# M885E.net
KiCad netlist of a schematic drawn in EAGLE
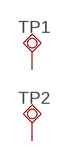
[diagram p0: schematic, sheet 1, part 1 of 2]
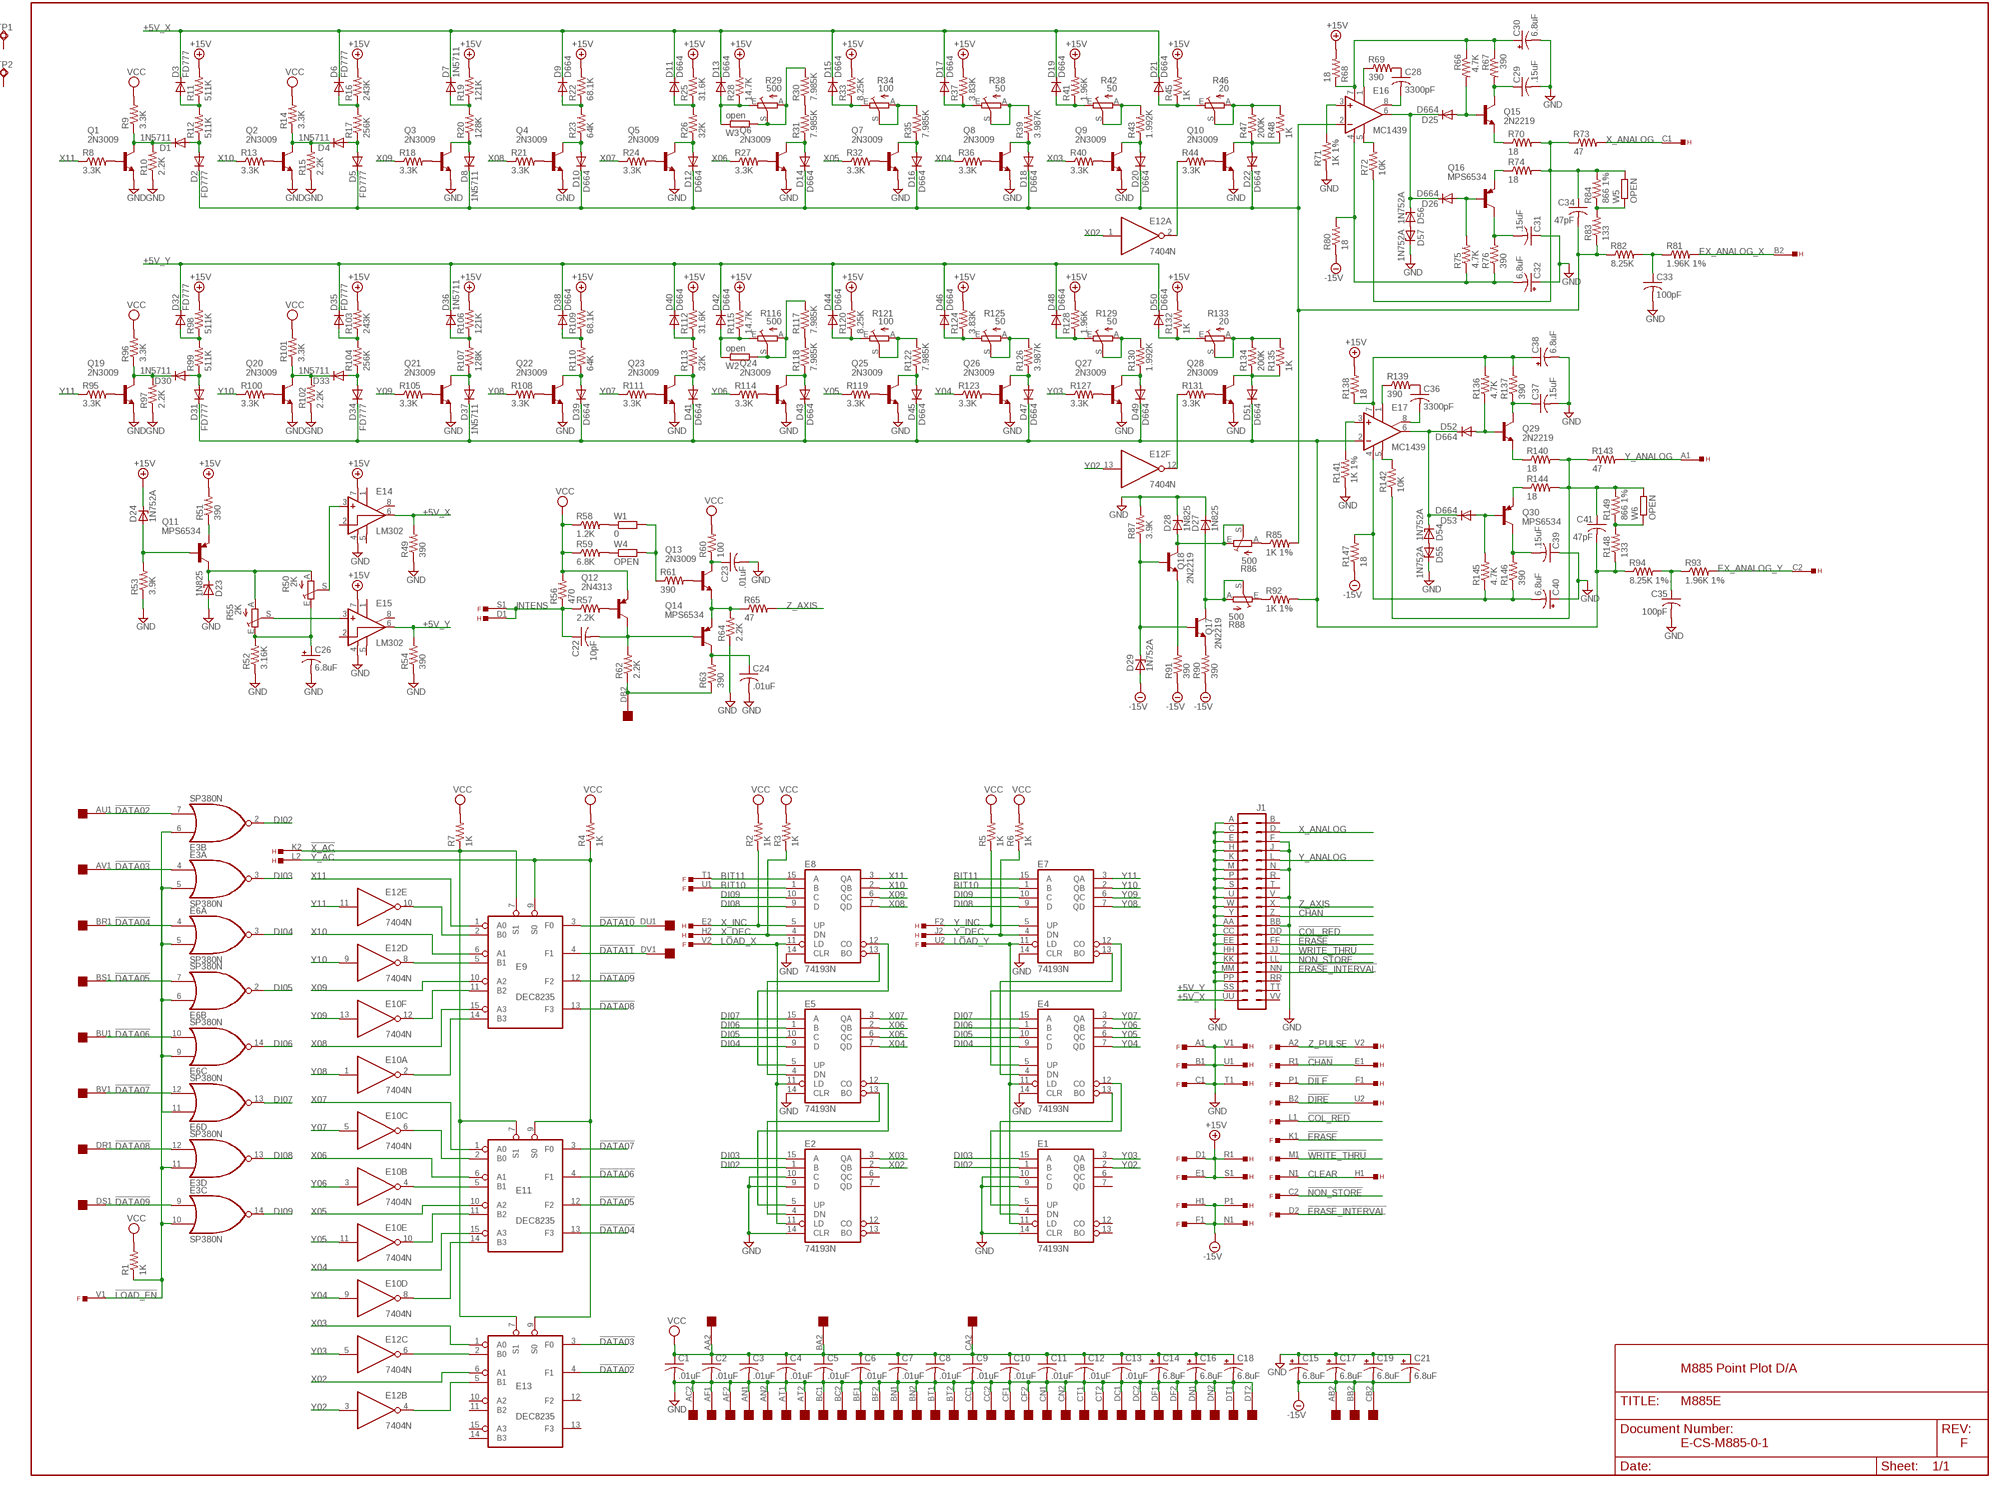
[diagram p1: schematic, sheet 1, part 2 of 2]

(export (version "E")
  (design (tool "Eeschema 10.0.6"))
  (components
    (comp (ref "C1")
      (value ".01uF")
      (footprint "eagle-import:C063-025X075")
      (libsource (lib "eagle-import") (part "C-US"))
    )
    (comp (ref "C2")
      (value ".01uF")
      (footprint "eagle-import:C063-025X075")
      (libsource (lib "eagle-import") (part "C-US"))
    )
    (comp (ref "C3")
      (value ".01uF")
      (footprint "eagle-import:C063-025X075")
      (libsource (lib "eagle-import") (part "C-US"))
    )
    (comp (ref "C4")
      (value ".01uF")
      (footprint "eagle-import:C063-025X075")
      (libsource (lib "eagle-import") (part "C-US"))
    )
    (comp (ref "C5")
      (value ".01uF")
      (footprint "eagle-import:C063-025X075")
      (libsource (lib "eagle-import") (part "C-US"))
    )
    (comp (ref "C6")
      (value ".01uF")
      (footprint "eagle-import:C063-025X075")
      (libsource (lib "eagle-import") (part "C-US"))
    )
    (comp (ref "C7")
      (value ".01uF")
      (footprint "eagle-import:C063-025X075")
      (libsource (lib "eagle-import") (part "C-US"))
    )
    (comp (ref "C8")
      (value ".01uF")
      (footprint "eagle-import:C063-025X075")
      (libsource (lib "eagle-import") (part "C-US"))
    )
    (comp (ref "C9")
      (value ".01uF")
      (footprint "eagle-import:C063-025X075")
      (libsource (lib "eagle-import") (part "C-US"))
    )
    (comp (ref "C10")
      (value ".01uF")
      (footprint "eagle-import:C063-025X075")
      (libsource (lib "eagle-import") (part "C-US"))
    )
    (comp (ref "C11")
      (value ".01uF")
      (footprint "eagle-import:C063-025X075")
      (libsource (lib "eagle-import") (part "C-US"))
    )
    (comp (ref "C12")
      (value ".01uF")
      (footprint "eagle-import:C063-025X075")
      (libsource (lib "eagle-import") (part "C-US"))
    )
    (comp (ref "C13")
      (value ".01uF")
      (footprint "eagle-import:C063-025X075")
      (libsource (lib "eagle-import") (part "C-US"))
    )
    (comp (ref "C14")
      (value "6.8uF")
      (footprint "eagle-import:E12-8")
      (libsource (lib "eagle-import") (part "CPOL-USE20-8AXIAL"))
    )
    (comp (ref "C15")
      (value "6.8uF")
      (footprint "eagle-import:E12-8")
      (libsource (lib "eagle-import") (part "CPOL-USE20-8AXIAL"))
    )
    (comp (ref "C16")
      (value "6.8uF")
      (footprint "eagle-import:E12-8")
      (libsource (lib "eagle-import") (part "CPOL-USE20-8AXIAL"))
    )
    (comp (ref "C17")
      (value "6.8uF")
      (footprint "eagle-import:E12-8")
      (libsource (lib "eagle-import") (part "CPOL-USE20-8AXIAL"))
    )
    (comp (ref "C18")
      (value "6.8uF")
      (footprint "eagle-import:E12-8")
      (libsource (lib "eagle-import") (part "CPOL-USE20-8AXIAL"))
    )
    (comp (ref "C19")
      (value "6.8uF")
      (footprint "eagle-import:E12-8")
      (libsource (lib "eagle-import") (part "CPOL-USE20-8AXIAL"))
    )
    (comp (ref "C21")
      (value "6.8uF")
      (footprint "eagle-import:E12-8")
      (libsource (lib "eagle-import") (part "CPOL-USE20-8AXIAL"))
    )
    (comp (ref "C22")
      (value "10pF")
      (footprint "eagle-import:C063-025X075")
      (libsource (lib "eagle-import") (part "C-US"))
    )
    (comp (ref "C23")
      (value ".01uF")
      (footprint "eagle-import:C063-025X075")
      (libsource (lib "eagle-import") (part "C-US"))
    )
    (comp (ref "C24")
      (value ".01uF")
      (footprint "eagle-import:C063-025X075")
      (libsource (lib "eagle-import") (part "C-US"))
    )
    (comp (ref "C26")
      (value "6.8uF")
      (footprint "eagle-import:E12-8")
      (libsource (lib "eagle-import") (part "CPOL-USE20-8AXIAL"))
    )
    (comp (ref "C28")
      (value "3300pF")
      (footprint "eagle-import:C150-054X183")
      (libsource (lib "eagle-import") (part "C-US150-054X183"))
    )
    (comp (ref "C29")
      (value ".15uF")
      (footprint "eagle-import:C150-054X183")
      (libsource (lib "eagle-import") (part "C-US150-054X183"))
    )
    (comp (ref "C30")
      (value "6.8uF")
      (footprint "eagle-import:E12-8")
      (libsource (lib "eagle-import") (part "CPOL-USE20-8AXIAL"))
    )
    (comp (ref "C31")
      (value ".15uF")
      (footprint "eagle-import:C150-054X183")
      (libsource (lib "eagle-import") (part "C-US150-054X183"))
    )
    (comp (ref "C32")
      (value "6.8uF")
      (footprint "eagle-import:E12-8")
      (libsource (lib "eagle-import") (part "CPOL-USE20-8AXIAL"))
    )
    (comp (ref "C33")
      (value "100pF")
      (footprint "eagle-import:C063-025X075")
      (libsource (lib "eagle-import") (part "C-US"))
    )
    (comp (ref "C34")
      (value "47pF")
      (footprint "eagle-import:C063-025X075")
      (libsource (lib "eagle-import") (part "C-US"))
    )
    (comp (ref "C35")
      (value "100pF")
      (footprint "eagle-import:C063-025X075")
      (libsource (lib "eagle-import") (part "C-US"))
    )
    (comp (ref "C36")
      (value "3300pF")
      (footprint "eagle-import:C150-054X183")
      (libsource (lib "eagle-import") (part "C-US150-054X183"))
    )
    (comp (ref "C37")
      (value ".15uF")
      (footprint "eagle-import:C150-054X183")
      (libsource (lib "eagle-import") (part "C-US150-054X183"))
    )
    (comp (ref "C38")
      (value "6.8uF")
      (footprint "eagle-import:E12-8")
      (libsource (lib "eagle-import") (part "CPOL-USE20-8AXIAL"))
    )
    (comp (ref "C39")
      (value ".15uF")
      (footprint "eagle-import:C150-054X183")
      (libsource (lib "eagle-import") (part "C-US150-054X183"))
    )
    (comp (ref "C40")
      (value "6.8uF")
      (footprint "eagle-import:E12-8")
      (libsource (lib "eagle-import") (part "CPOL-USE20-8AXIAL"))
    )
    (comp (ref "C41")
      (value "47pF")
      (footprint "eagle-import:C063-025X075")
      (libsource (lib "eagle-import") (part "C-US"))
    )
    (comp (ref "D1")
      (value "1N5711")
      (footprint "eagle-import:DO35-10")
      (libsource (lib "eagle-import") (part "DIODE-DO35-10"))
    )
    (comp (ref "D2")
      (value "FD777")
      (footprint "eagle-import:DO35-10")
      (libsource (lib "eagle-import") (part "DIODE-DO35-10"))
    )
    (comp (ref "D3")
      (value "FD777")
      (footprint "eagle-import:DO35-10")
      (libsource (lib "eagle-import") (part "DIODE-DO35-10"))
    )
    (comp (ref "D4")
      (value "1N5711")
      (footprint "eagle-import:DO35-10")
      (libsource (lib "eagle-import") (part "DIODE-DO35-10"))
    )
    (comp (ref "D5")
      (value "FD777")
      (footprint "eagle-import:DO35-10")
      (libsource (lib "eagle-import") (part "DIODE-DO35-10"))
    )
    (comp (ref "D6")
      (value "FD777")
      (footprint "eagle-import:DO35-10")
      (libsource (lib "eagle-import") (part "DIODE-DO35-10"))
    )
    (comp (ref "D7")
      (value "1N5711")
      (footprint "eagle-import:DO35-10")
      (libsource (lib "eagle-import") (part "DIODE-DO35-10"))
    )
    (comp (ref "D8")
      (value "1N5711")
      (footprint "eagle-import:DO35-10")
      (libsource (lib "eagle-import") (part "DIODE-DO35-10"))
    )
    (comp (ref "D9")
      (value "D664")
      (footprint "eagle-import:DO35-10")
      (libsource (lib "eagle-import") (part "DIODE-DO35-10"))
    )
    (comp (ref "D10")
      (value "D664")
      (footprint "eagle-import:DO35-10")
      (libsource (lib "eagle-import") (part "DIODE-DO35-10"))
    )
    (comp (ref "D11")
      (value "D664")
      (footprint "eagle-import:DO35-10")
      (libsource (lib "eagle-import") (part "DIODE-DO35-10"))
    )
    (comp (ref "D12")
      (value "D664")
      (footprint "eagle-import:DO35-10")
      (libsource (lib "eagle-import") (part "DIODE-DO35-10"))
    )
    (comp (ref "D13")
      (value "D664")
      (footprint "eagle-import:DO35-10")
      (libsource (lib "eagle-import") (part "DIODE-DO35-10"))
    )
    (comp (ref "D14")
      (value "D664")
      (footprint "eagle-import:DO35-10")
      (libsource (lib "eagle-import") (part "DIODE-DO35-10"))
    )
    (comp (ref "D15")
      (value "D664")
      (footprint "eagle-import:DO35-10")
      (libsource (lib "eagle-import") (part "DIODE-DO35-10"))
    )
    (comp (ref "D16")
      (value "D664")
      (footprint "eagle-import:DO35-10")
      (libsource (lib "eagle-import") (part "DIODE-DO35-10"))
    )
    (comp (ref "D17")
      (value "D664")
      (footprint "eagle-import:DO35-10")
      (libsource (lib "eagle-import") (part "DIODE-DO35-10"))
    )
    (comp (ref "D18")
      (value "D664")
      (footprint "eagle-import:DO35-10")
      (libsource (lib "eagle-import") (part "DIODE-DO35-10"))
    )
    (comp (ref "D19")
      (value "D664")
      (footprint "eagle-import:DO35-10")
      (libsource (lib "eagle-import") (part "DIODE-DO35-10"))
    )
    (comp (ref "D20")
      (value "D664")
      (footprint "eagle-import:DO35-10")
      (libsource (lib "eagle-import") (part "DIODE-DO35-10"))
    )
    (comp (ref "D21")
      (value "D664")
      (footprint "eagle-import:DO35-10")
      (libsource (lib "eagle-import") (part "DIODE-DO35-10"))
    )
    (comp (ref "D22")
      (value "D664")
      (footprint "eagle-import:DO35-10")
      (libsource (lib "eagle-import") (part "DIODE-DO35-10"))
    )
    (comp (ref "D23")
      (value "1N825")
      (footprint "eagle-import:DO35Z10")
      (libsource (lib "eagle-import") (part "ZENER-DIODEDO35Z10"))
    )
    (comp (ref "D24")
      (value "1N752A")
      (footprint "eagle-import:DO35Z10")
      (libsource (lib "eagle-import") (part "ZENER-DIODEDO35Z10"))
    )
    (comp (ref "D25")
      (value "D664")
      (footprint "eagle-import:DO35-10")
      (libsource (lib "eagle-import") (part "DIODE-DO35-10"))
    )
    (comp (ref "D26")
      (value "D664")
      (footprint "eagle-import:DO35-10")
      (libsource (lib "eagle-import") (part "DIODE-DO35-10"))
    )
    (comp (ref "D27")
      (value "1N825")
      (footprint "eagle-import:DO35Z10")
      (libsource (lib "eagle-import") (part "ZENER-DIODEDO35Z10"))
    )
    (comp (ref "D28")
      (value "1N825")
      (footprint "eagle-import:DO35Z10")
      (libsource (lib "eagle-import") (part "ZENER-DIODEDO35Z10"))
    )
    (comp (ref "D29")
      (value "1N752A")
      (footprint "eagle-import:DO35Z10")
      (libsource (lib "eagle-import") (part "ZENER-DIODEDO35Z10"))
    )
    (comp (ref "D30")
      (value "1N5711")
      (footprint "eagle-import:DO35-10")
      (libsource (lib "eagle-import") (part "DIODE-DO35-10"))
    )
    (comp (ref "D31")
      (value "FD777")
      (footprint "eagle-import:DO35-10")
      (libsource (lib "eagle-import") (part "DIODE-DO35-10"))
    )
    (comp (ref "D32")
      (value "FD777")
      (footprint "eagle-import:DO35-10")
      (libsource (lib "eagle-import") (part "DIODE-DO35-10"))
    )
    (comp (ref "D33")
      (value "1N5711")
      (footprint "eagle-import:DO35-10")
      (libsource (lib "eagle-import") (part "DIODE-DO35-10"))
    )
    (comp (ref "D34")
      (value "FD777")
      (footprint "eagle-import:DO35-10")
      (libsource (lib "eagle-import") (part "DIODE-DO35-10"))
    )
    (comp (ref "D35")
      (value "FD777")
      (footprint "eagle-import:DO35-10")
      (libsource (lib "eagle-import") (part "DIODE-DO35-10"))
    )
    (comp (ref "D36")
      (value "1N5711")
      (footprint "eagle-import:DO35-10")
      (libsource (lib "eagle-import") (part "DIODE-DO35-10"))
    )
    (comp (ref "D37")
      (value "1N5711")
      (footprint "eagle-import:DO35-10")
      (libsource (lib "eagle-import") (part "DIODE-DO35-10"))
    )
    (comp (ref "D38")
      (value "D664")
      (footprint "eagle-import:DO35-10")
      (libsource (lib "eagle-import") (part "DIODE-DO35-10"))
    )
    (comp (ref "D39")
      (value "D664")
      (footprint "eagle-import:DO35-10")
      (libsource (lib "eagle-import") (part "DIODE-DO35-10"))
    )
    (comp (ref "D40")
      (value "D664")
      (footprint "eagle-import:DO35-10")
      (libsource (lib "eagle-import") (part "DIODE-DO35-10"))
    )
    (comp (ref "D41")
      (value "D664")
      (footprint "eagle-import:DO35-10")
      (libsource (lib "eagle-import") (part "DIODE-DO35-10"))
    )
    (comp (ref "D42")
      (value "D664")
      (footprint "eagle-import:DO35-10")
      (libsource (lib "eagle-import") (part "DIODE-DO35-10"))
    )
    (comp (ref "D43")
      (value "D664")
      (footprint "eagle-import:DO35-10")
      (libsource (lib "eagle-import") (part "DIODE-DO35-10"))
    )
    (comp (ref "D44")
      (value "D664")
      (footprint "eagle-import:DO35-10")
      (libsource (lib "eagle-import") (part "DIODE-DO35-10"))
    )
    (comp (ref "D45")
      (value "D664")
      (footprint "eagle-import:DO35-10")
      (libsource (lib "eagle-import") (part "DIODE-DO35-10"))
    )
    (comp (ref "D46")
      (value "D664")
      (footprint "eagle-import:DO35-10")
      (libsource (lib "eagle-import") (part "DIODE-DO35-10"))
    )
    (comp (ref "D47")
      (value "D664")
      (footprint "eagle-import:DO35-10")
      (libsource (lib "eagle-import") (part "DIODE-DO35-10"))
    )
    (comp (ref "D48")
      (value "D664")
      (footprint "eagle-import:DO35-10")
      (libsource (lib "eagle-import") (part "DIODE-DO35-10"))
    )
    (comp (ref "D49")
      (value "D664")
      (footprint "eagle-import:DO35-10")
      (libsource (lib "eagle-import") (part "DIODE-DO35-10"))
    )
    (comp (ref "D50")
      (value "D664")
      (footprint "eagle-import:DO35-10")
      (libsource (lib "eagle-import") (part "DIODE-DO35-10"))
    )
    (comp (ref "D51")
      (value "D664")
      (footprint "eagle-import:DO35-10")
      (libsource (lib "eagle-import") (part "DIODE-DO35-10"))
    )
    (comp (ref "D52")
      (value "D664")
      (footprint "eagle-import:DO35-10")
      (libsource (lib "eagle-import") (part "DIODE-DO35-10"))
    )
    (comp (ref "D53")
      (value "D664")
      (footprint "eagle-import:DO35-10")
      (libsource (lib "eagle-import") (part "DIODE-DO35-10"))
    )
    (comp (ref "D54")
      (value "1N752A")
      (footprint "eagle-import:DO35Z10")
      (libsource (lib "eagle-import") (part "ZENER-DIODEDO35Z10"))
    )
    (comp (ref "D55")
      (value "1N752A")
      (footprint "eagle-import:DO35Z10")
      (libsource (lib "eagle-import") (part "ZENER-DIODEDO35Z10"))
    )
    (comp (ref "D56")
      (value "1N752A")
      (footprint "eagle-import:DO35Z10")
      (libsource (lib "eagle-import") (part "ZENER-DIODEDO35Z10"))
    )
    (comp (ref "D57")
      (value "1N752A")
      (footprint "eagle-import:DO35Z10")
      (libsource (lib "eagle-import") (part "ZENER-DIODEDO35Z10"))
    )
    (comp (ref "E1")
      (value "74193N")
      (footprint "eagle-import:DIL16")
      (libsource (lib "eagle-import") (part "74193N"))
    )
    (comp (ref "E2")
      (value "74193N")
      (footprint "eagle-import:DIL16")
      (libsource (lib "eagle-import") (part "74193N"))
    )
    (comp (ref "E3")
      (value "SP380N")
      (footprint "eagle-import:DIL14")
      (libsource (lib "eagle-import") (part "SP380N"))
    )
    (comp (ref "E4")
      (value "74193N")
      (footprint "eagle-import:DIL16")
      (libsource (lib "eagle-import") (part "74193N"))
    )
    (comp (ref "E5")
      (value "74193N")
      (footprint "eagle-import:DIL16")
      (libsource (lib "eagle-import") (part "74193N"))
    )
    (comp (ref "E6")
      (value "SP380N")
      (footprint "eagle-import:DIL14")
      (libsource (lib "eagle-import") (part "SP380N"))
    )
    (comp (ref "E7")
      (value "74193N")
      (footprint "eagle-import:DIL16")
      (libsource (lib "eagle-import") (part "74193N"))
    )
    (comp (ref "E8")
      (value "74193N")
      (footprint "eagle-import:DIL16")
      (libsource (lib "eagle-import") (part "74193N"))
    )
    (comp (ref "E9")
      (value "DEC8235")
      (footprint "eagle-import:DIL16")
      (libsource (lib "eagle-import") (part "DEC8235"))
    )
    (comp (ref "E10")
      (value "7404N")
      (footprint "eagle-import:DIL14")
      (libsource (lib "eagle-import") (part "7404N"))
    )
    (comp (ref "E11")
      (value "DEC8235")
      (footprint "eagle-import:DIL16")
      (libsource (lib "eagle-import") (part "DEC8235"))
    )
    (comp (ref "E12")
      (value "7404N")
      (footprint "eagle-import:DIL14")
      (libsource (lib "eagle-import") (part "7404N"))
    )
    (comp (ref "E13")
      (value "DEC8235")
      (footprint "eagle-import:DIL16")
      (libsource (lib "eagle-import") (part "DEC8235"))
    )
    (comp (ref "E14")
      (value "LM302")
      (footprint "eagle-import:TO99")
      (libsource (lib "eagle-import") (part "AD504H"))
    )
    (comp (ref "E15")
      (value "LM302")
      (footprint "eagle-import:TO99")
      (libsource (lib "eagle-import") (part "AD504H"))
    )
    (comp (ref "E16")
      (value "MC1439")
      (footprint "eagle-import:TO99")
      (libsource (lib "eagle-import") (part "AD504H"))
    )
    (comp (ref "E17")
      (value "MC1439")
      (footprint "eagle-import:TO99")
      (libsource (lib "eagle-import") (part "AD504H"))
    )
    (comp (ref "F")
      (value "EDGE-TOP")
      (footprint "eagle-import:EDGE-CON2")
      (libsource (lib "eagle-import") (part "EDGE-TOP"))
    )
    (comp (ref "H")
      (value "EDGE-TOP")
      (footprint "eagle-import:EDGE-CON2")
      (libsource (lib "eagle-import") (part "EDGE-TOP"))
    )
    (comp (ref "J1")
      (value "DEC40PINH")
      (footprint "eagle-import:DEC40PINH")
      (libsource (lib "eagle-import") (part "DEC40PINH"))
    )
    (comp (ref "OMNIBUS")
      (value "QUAD")
      (footprint "eagle-import:EDGE-CON8")
      (libsource (lib "eagle-import") (part "QUAD"))
    )
    (comp (ref "Q1")
      (value "2N3009")
      (footprint "eagle-import:TO5")
      (libsource (lib "eagle-import") (part "-NPN-TO5"))
    )
    (comp (ref "Q2")
      (value "2N3009")
      (footprint "eagle-import:TO5")
      (libsource (lib "eagle-import") (part "-NPN-TO5"))
    )
    (comp (ref "Q3")
      (value "2N3009")
      (footprint "eagle-import:TO5")
      (libsource (lib "eagle-import") (part "-NPN-TO5"))
    )
    (comp (ref "Q4")
      (value "2N3009")
      (footprint "eagle-import:TO5")
      (libsource (lib "eagle-import") (part "-NPN-TO5"))
    )
    (comp (ref "Q5")
      (value "2N3009")
      (footprint "eagle-import:TO5")
      (libsource (lib "eagle-import") (part "-NPN-TO5"))
    )
    (comp (ref "Q6")
      (value "2N3009")
      (footprint "eagle-import:TO5")
      (libsource (lib "eagle-import") (part "-NPN-TO5"))
    )
    (comp (ref "Q7")
      (value "2N3009")
      (footprint "eagle-import:TO5")
      (libsource (lib "eagle-import") (part "-NPN-TO5"))
    )
    (comp (ref "Q8")
      (value "2N3009")
      (footprint "eagle-import:TO5")
      (libsource (lib "eagle-import") (part "-NPN-TO5"))
    )
    (comp (ref "Q9")
      (value "2N3009")
      (footprint "eagle-import:TO5")
      (libsource (lib "eagle-import") (part "-NPN-TO5"))
    )
    (comp (ref "Q10")
      (value "2N3009")
      (footprint "eagle-import:TO5")
      (libsource (lib "eagle-import") (part "-NPN-TO5"))
    )
    (comp (ref "Q11")
      (value "MPS6534")
      (footprint "eagle-import:TO5")
      (libsource (lib "eagle-import") (part "-PNP-TO5"))
    )
    (comp (ref "Q12")
      (value "2N4313")
      (footprint "eagle-import:TO5")
      (libsource (lib "eagle-import") (part "-PNP-TO5"))
    )
    (comp (ref "Q13")
      (value "2N3009")
      (footprint "eagle-import:TO5")
      (libsource (lib "eagle-import") (part "-NPN-TO5"))
    )
    (comp (ref "Q14")
      (value "MPS6534")
      (footprint "eagle-import:TO5")
      (libsource (lib "eagle-import") (part "-PNP-TO5"))
    )
    (comp (ref "Q15")
      (value "2N2219")
      (footprint "eagle-import:TO5")
      (libsource (lib "eagle-import") (part "-NPN-TO5"))
    )
    (comp (ref "Q16")
      (value "MPS6534")
      (footprint "eagle-import:TO5")
      (libsource (lib "eagle-import") (part "-PNP-TO5"))
    )
    (comp (ref "Q17")
      (value "2N2219")
      (footprint "eagle-import:TO5")
      (libsource (lib "eagle-import") (part "-NPN-TO5"))
    )
    (comp (ref "Q18")
      (value "2N2219")
      (footprint "eagle-import:TO5")
      (libsource (lib "eagle-import") (part "-NPN-TO5"))
    )
    (comp (ref "Q19")
      (value "2N3009")
      (footprint "eagle-import:TO5")
      (libsource (lib "eagle-import") (part "-NPN-TO5"))
    )
    (comp (ref "Q20")
      (value "2N3009")
      (footprint "eagle-import:TO5")
      (libsource (lib "eagle-import") (part "-NPN-TO5"))
    )
    (comp (ref "Q21")
      (value "2N3009")
      (footprint "eagle-import:TO5")
      (libsource (lib "eagle-import") (part "-NPN-TO5"))
    )
    (comp (ref "Q22")
      (value "2N3009")
      (footprint "eagle-import:TO5")
      (libsource (lib "eagle-import") (part "-NPN-TO5"))
    )
    (comp (ref "Q23")
      (value "2N3009")
      (footprint "eagle-import:TO5")
      (libsource (lib "eagle-import") (part "-NPN-TO5"))
    )
    (comp (ref "Q24")
      (value "2N3009")
      (footprint "eagle-import:TO5")
      (libsource (lib "eagle-import") (part "-NPN-TO5"))
    )
    (comp (ref "Q25")
      (value "2N3009")
      (footprint "eagle-import:TO5")
      (libsource (lib "eagle-import") (part "-NPN-TO5"))
    )
    (comp (ref "Q26")
      (value "2N3009")
      (footprint "eagle-import:TO5")
      (libsource (lib "eagle-import") (part "-NPN-TO5"))
    )
    (comp (ref "Q27")
      (value "2N3009")
      (footprint "eagle-import:TO5")
      (libsource (lib "eagle-import") (part "-NPN-TO5"))
    )
    (comp (ref "Q28")
      (value "2N3009")
      (footprint "eagle-import:TO5")
      (libsource (lib "eagle-import") (part "-NPN-TO5"))
    )
    (comp (ref "Q29")
      (value "2N2219")
      (footprint "eagle-import:TO5")
      (libsource (lib "eagle-import") (part "-NPN-TO5"))
    )
    (comp (ref "Q30")
      (value "MPS6534")
      (footprint "eagle-import:TO5")
      (libsource (lib "eagle-import") (part "-PNP-TO5"))
    )
    (comp (ref "R1")
      (value "1K")
      (footprint "eagle-import:0207_10")
      (libsource (lib "eagle-import") (part "R-US_0207/10"))
    )
    (comp (ref "R2")
      (value "1K")
      (footprint "eagle-import:0207_10")
      (libsource (lib "eagle-import") (part "R-US_0207/10"))
    )
    (comp (ref "R3")
      (value "1K")
      (footprint "eagle-import:0207_10")
      (libsource (lib "eagle-import") (part "R-US_0207/10"))
    )
    (comp (ref "R4")
      (value "1K")
      (footprint "eagle-import:0207_10")
      (libsource (lib "eagle-import") (part "R-US_0207/10"))
    )
    (comp (ref "R5")
      (value "1K")
      (footprint "eagle-import:0207_10")
      (libsource (lib "eagle-import") (part "R-US_0207/10"))
    )
    (comp (ref "R6")
      (value "1K")
      (footprint "eagle-import:0207_10")
      (libsource (lib "eagle-import") (part "R-US_0207/10"))
    )
    (comp (ref "R7")
      (value "1K")
      (footprint "eagle-import:0207_10")
      (libsource (lib "eagle-import") (part "R-US_0207/10"))
    )
    (comp (ref "R8")
      (value "3.3K")
      (footprint "eagle-import:0207_10")
      (libsource (lib "eagle-import") (part "R-US_0207/10"))
    )
    (comp (ref "R9")
      (value "3.3K")
      (footprint "eagle-import:0207_10")
      (libsource (lib "eagle-import") (part "R-US_0207/10"))
    )
    (comp (ref "R10")
      (value "2.2K")
      (footprint "eagle-import:0207_10")
      (libsource (lib "eagle-import") (part "R-US_0207/10"))
    )
    (comp (ref "R11")
      (value "511K")
      (footprint "eagle-import:0207_15")
      (libsource (lib "eagle-import") (part "R-US_0207/15"))
    )
    (comp (ref "R12")
      (value "511K")
      (footprint "eagle-import:0207_15")
      (libsource (lib "eagle-import") (part "R-US_0207/15"))
    )
    (comp (ref "R13")
      (value "3.3K")
      (footprint "eagle-import:0207_10")
      (libsource (lib "eagle-import") (part "R-US_0207/10"))
    )
    (comp (ref "R14")
      (value "3.3K")
      (footprint "eagle-import:0207_10")
      (libsource (lib "eagle-import") (part "R-US_0207/10"))
    )
    (comp (ref "R15")
      (value "2.2K")
      (footprint "eagle-import:0207_10")
      (libsource (lib "eagle-import") (part "R-US_0207/10"))
    )
    (comp (ref "R16")
      (value "243K")
      (footprint "eagle-import:0207_15")
      (libsource (lib "eagle-import") (part "R-US_0207/15"))
    )
    (comp (ref "R17")
      (value "256K")
      (footprint "eagle-import:0207_15")
      (libsource (lib "eagle-import") (part "R-US_0207/15"))
    )
    (comp (ref "R18")
      (value "3.3K")
      (footprint "eagle-import:0207_10")
      (libsource (lib "eagle-import") (part "R-US_0207/10"))
    )
    (comp (ref "R19")
      (value "121K")
      (footprint "eagle-import:0207_15")
      (libsource (lib "eagle-import") (part "R-US_0207/15"))
    )
    (comp (ref "R20")
      (value "128K")
      (footprint "eagle-import:0207_15")
      (libsource (lib "eagle-import") (part "R-US_0207/15"))
    )
    (comp (ref "R21")
      (value "3.3K")
      (footprint "eagle-import:0207_10")
      (libsource (lib "eagle-import") (part "R-US_0207/10"))
    )
    (comp (ref "R22")
      (value "68.1K")
      (footprint "eagle-import:0207_15")
      (libsource (lib "eagle-import") (part "R-US_0207/15"))
    )
    (comp (ref "R23")
      (value "64K")
      (footprint "eagle-import:0207_15")
      (libsource (lib "eagle-import") (part "R-US_0207/15"))
    )
    (comp (ref "R24")
      (value "3.3K")
      (footprint "eagle-import:0207_10")
      (libsource (lib "eagle-import") (part "R-US_0207/10"))
    )
    (comp (ref "R25")
      (value "31.6K")
      (footprint "eagle-import:0207_15")
      (libsource (lib "eagle-import") (part "R-US_0207/15"))
    )
    (comp (ref "R26")
      (value "32K")
      (footprint "eagle-import:0207_15")
      (libsource (lib "eagle-import") (part "R-US_0207/15"))
    )
    (comp (ref "R27")
      (value "3.3K")
      (footprint "eagle-import:0207_10")
      (libsource (lib "eagle-import") (part "R-US_0207/10"))
    )
    (comp (ref "R28")
      (value "14.7K")
      (footprint "eagle-import:0207_15")
      (libsource (lib "eagle-import") (part "R-US_0207/15"))
    )
    (comp (ref "R29")
      (value "500")
      (footprint "eagle-import:S75P")
      (libsource (lib "eagle-import") (part "TRIM_EU-S75P"))
    )
    (comp (ref "R30")
      (value "7.985K")
      (footprint "eagle-import:0207_15")
      (libsource (lib "eagle-import") (part "R-US_0207/15"))
    )
    (comp (ref "R31")
      (value "7.985K")
      (footprint "eagle-import:0207_15")
      (libsource (lib "eagle-import") (part "R-US_0207/15"))
    )
    (comp (ref "R32")
      (value "3.3K")
      (footprint "eagle-import:0207_10")
      (libsource (lib "eagle-import") (part "R-US_0207/10"))
    )
    (comp (ref "R33")
      (value "8.25K")
      (footprint "eagle-import:0207_15")
      (libsource (lib "eagle-import") (part "R-US_0207/15"))
    )
    (comp (ref "R34")
      (value "100")
      (footprint "eagle-import:S75P")
      (libsource (lib "eagle-import") (part "TRIM_EU-S75P"))
    )
    (comp (ref "R35")
      (value "7.985K")
      (footprint "eagle-import:0207_15")
      (libsource (lib "eagle-import") (part "R-US_0207/15"))
    )
    (comp (ref "R36")
      (value "3.3K")
      (footprint "eagle-import:0207_10")
      (libsource (lib "eagle-import") (part "R-US_0207/10"))
    )
    (comp (ref "R37")
      (value "3.83K")
      (footprint "eagle-import:0207_15")
      (libsource (lib "eagle-import") (part "R-US_0207/15"))
    )
    (comp (ref "R38")
      (value "50")
      (footprint "eagle-import:S75P")
      (libsource (lib "eagle-import") (part "TRIM_EU-S75P"))
    )
    (comp (ref "R39")
      (value "3.987K")
      (footprint "eagle-import:0207_15")
      (libsource (lib "eagle-import") (part "R-US_0207/15"))
    )
    (comp (ref "R40")
      (value "3.3K")
      (footprint "eagle-import:0207_10")
      (libsource (lib "eagle-import") (part "R-US_0207/10"))
    )
    (comp (ref "R41")
      (value "1.96K")
      (footprint "eagle-import:0207_15")
      (libsource (lib "eagle-import") (part "R-US_0207/15"))
    )
    (comp (ref "R42")
      (value "50")
      (footprint "eagle-import:S75P")
      (libsource (lib "eagle-import") (part "TRIM_EU-S75P"))
    )
    (comp (ref "R43")
      (value "1.992K")
      (footprint "eagle-import:0207_15")
      (libsource (lib "eagle-import") (part "R-US_0207/15"))
    )
    (comp (ref "R44")
      (value "3.3K")
      (footprint "eagle-import:0207_10")
      (libsource (lib "eagle-import") (part "R-US_0207/10"))
    )
    (comp (ref "R45")
      (value "1K")
      (footprint "eagle-import:0207_15")
      (libsource (lib "eagle-import") (part "R-US_0207/15"))
    )
    (comp (ref "R46")
      (value "20")
      (footprint "eagle-import:S75P")
      (libsource (lib "eagle-import") (part "TRIM_EU-S75P"))
    )
    (comp (ref "R47")
      (value "200K")
      (footprint "eagle-import:0207_15")
      (libsource (lib "eagle-import") (part "R-US_0207/15"))
    )
    (comp (ref "R48")
      (value "1K")
      (footprint "eagle-import:0207_15")
      (libsource (lib "eagle-import") (part "R-US_0207/15"))
    )
    (comp (ref "R49")
      (value "390")
      (footprint "eagle-import:0207_10")
      (libsource (lib "eagle-import") (part "R-US_0207/10"))
    )
    (comp (ref "R50")
      (value "2K")
      (footprint "eagle-import:SP19L")
      (libsource (lib "eagle-import") (part "TRIM_EU-B90P"))
    )
    (comp (ref "R51")
      (value "390")
      (footprint "eagle-import:0207_10")
      (libsource (lib "eagle-import") (part "R-US_0207/10"))
    )
    (comp (ref "R52")
      (value "3.16K")
      (footprint "eagle-import:0207_15")
      (libsource (lib "eagle-import") (part "R-US_0207/15"))
    )
    (comp (ref "R53")
      (value "3.9K")
      (footprint "eagle-import:0207_10")
      (libsource (lib "eagle-import") (part "R-US_0207/10"))
    )
    (comp (ref "R54")
      (value "390")
      (footprint "eagle-import:0207_10")
      (libsource (lib "eagle-import") (part "R-US_0207/10"))
    )
    (comp (ref "R55")
      (value "2K")
      (footprint "eagle-import:SP19L")
      (libsource (lib "eagle-import") (part "TRIM_EU-B90P"))
    )
    (comp (ref "R56")
      (value "470")
      (footprint "eagle-import:0207_10")
      (libsource (lib "eagle-import") (part "R-US_0207/10"))
    )
    (comp (ref "R57")
      (value "2.2K")
      (footprint "eagle-import:0207_10")
      (libsource (lib "eagle-import") (part "R-US_0207/10"))
    )
    (comp (ref "R58")
      (value "1.2K")
      (footprint "eagle-import:0207_10")
      (libsource (lib "eagle-import") (part "R-US_0207/10"))
    )
    (comp (ref "R59")
      (value "6.8K")
      (footprint "eagle-import:0207_10")
      (libsource (lib "eagle-import") (part "R-US_0207/10"))
    )
    (comp (ref "R60")
      (value "100")
      (footprint "eagle-import:0207_10")
      (libsource (lib "eagle-import") (part "R-US_0207/10"))
    )
    (comp (ref "R61")
      (value "390")
      (footprint "eagle-import:0207_10")
      (libsource (lib "eagle-import") (part "R-US_0207/10"))
    )
    (comp (ref "R62")
      (value "2.2K")
      (footprint "eagle-import:0207_10")
      (libsource (lib "eagle-import") (part "R-US_0207/10"))
    )
    (comp (ref "R63")
      (value "390")
      (footprint "eagle-import:0207_10")
      (libsource (lib "eagle-import") (part "R-US_0207/10"))
    )
    (comp (ref "R64")
      (value "2.2K")
      (footprint "eagle-import:0207_10")
      (libsource (lib "eagle-import") (part "R-US_0207/10"))
    )
    (comp (ref "R65")
      (value "47")
      (footprint "eagle-import:0207_10")
      (libsource (lib "eagle-import") (part "R-US_0207/10"))
    )
    (comp (ref "R66")
      (value "4.7K")
      (footprint "eagle-import:0207_10")
      (libsource (lib "eagle-import") (part "R-US_0207/10"))
    )
    (comp (ref "R67")
      (value "390")
      (footprint "eagle-import:0207_10")
      (libsource (lib "eagle-import") (part "R-US_0207/10"))
    )
    (comp (ref "R68")
      (value "18")
      (footprint "eagle-import:0207_10")
      (libsource (lib "eagle-import") (part "R-US_0207/10"))
    )
    (comp (ref "R69")
      (value "390")
      (footprint "eagle-import:0207_10")
      (libsource (lib "eagle-import") (part "R-US_0207/10"))
    )
    (comp (ref "R70")
      (value "18")
      (footprint "eagle-import:0207_10")
      (libsource (lib "eagle-import") (part "R-US_0207/10"))
    )
    (comp (ref "R71")
      (value "1K 1%")
      (footprint "eagle-import:0207_15")
      (libsource (lib "eagle-import") (part "R-US_0207/15"))
    )
    (comp (ref "R72")
      (value "10K")
      (footprint "eagle-import:0207_10")
      (libsource (lib "eagle-import") (part "R-US_0207/10"))
    )
    (comp (ref "R73")
      (value "47")
      (footprint "eagle-import:0207_10")
      (libsource (lib "eagle-import") (part "R-US_0207/10"))
    )
    (comp (ref "R74")
      (value "18")
      (footprint "eagle-import:0207_10")
      (libsource (lib "eagle-import") (part "R-US_0207/10"))
    )
    (comp (ref "R75")
      (value "4.7K")
      (footprint "eagle-import:0207_10")
      (libsource (lib "eagle-import") (part "R-US_0207/10"))
    )
    (comp (ref "R76")
      (value "390")
      (footprint "eagle-import:0207_10")
      (libsource (lib "eagle-import") (part "R-US_0207/10"))
    )
    (comp (ref "R80")
      (value "18")
      (footprint "eagle-import:0207_10")
      (libsource (lib "eagle-import") (part "R-US_0207/10"))
    )
    (comp (ref "R81")
      (value "1.96K 1%")
      (footprint "eagle-import:0207_15")
      (libsource (lib "eagle-import") (part "R-US_0207/15"))
    )
    (comp (ref "R82")
      (value "8.25K")
      (footprint "eagle-import:0207_15")
      (libsource (lib "eagle-import") (part "R-US_0207/15"))
    )
    (comp (ref "R83")
      (value "133")
      (footprint "eagle-import:0207_15")
      (libsource (lib "eagle-import") (part "R-US_0207/15"))
    )
    (comp (ref "R84")
      (value "866 1%")
      (footprint "eagle-import:0207_15")
      (libsource (lib "eagle-import") (part "R-US_0207/15"))
    )
    (comp (ref "R85")
      (value "1K 1%")
      (footprint "eagle-import:0207_15")
      (libsource (lib "eagle-import") (part "R-US_0207/15"))
    )
    (comp (ref "R86")
      (value "500")
      (footprint "eagle-import:SP19L")
      (libsource (lib "eagle-import") (part "TRIM_EU-B90P"))
    )
    (comp (ref "R87")
      (value "3.9K")
      (footprint "eagle-import:0207_10")
      (libsource (lib "eagle-import") (part "R-US_0207/10"))
    )
    (comp (ref "R88")
      (value "500")
      (footprint "eagle-import:SP19L")
      (libsource (lib "eagle-import") (part "TRIM_EU-B90P"))
    )
    (comp (ref "R90")
      (value "390")
      (footprint "eagle-import:0207_10")
      (libsource (lib "eagle-import") (part "R-US_0207/10"))
    )
    (comp (ref "R91")
      (value "390")
      (footprint "eagle-import:0207_10")
      (libsource (lib "eagle-import") (part "R-US_0207/10"))
    )
    (comp (ref "R92")
      (value "1K 1%")
      (footprint "eagle-import:0207_15")
      (libsource (lib "eagle-import") (part "R-US_0207/15"))
    )
    (comp (ref "R93")
      (value "1.96K 1%")
      (footprint "eagle-import:0207_15")
      (libsource (lib "eagle-import") (part "R-US_0207/15"))
    )
    (comp (ref "R94")
      (value "8.25K 1%")
      (footprint "eagle-import:0207_10")
      (libsource (lib "eagle-import") (part "R-US_0207/10"))
    )
    (comp (ref "R95")
      (value "3.3K")
      (footprint "eagle-import:0207_10")
      (libsource (lib "eagle-import") (part "R-US_0207/10"))
    )
    (comp (ref "R96")
      (value "3.3K")
      (footprint "eagle-import:0207_10")
      (libsource (lib "eagle-import") (part "R-US_0207/10"))
    )
    (comp (ref "R97")
      (value "2.2K")
      (footprint "eagle-import:0207_10")
      (libsource (lib "eagle-import") (part "R-US_0207/10"))
    )
    (comp (ref "R98")
      (value "511K")
      (footprint "eagle-import:0207_15")
      (libsource (lib "eagle-import") (part "R-US_0207/15"))
    )
    (comp (ref "R99")
      (value "511K")
      (footprint "eagle-import:0207_15")
      (libsource (lib "eagle-import") (part "R-US_0207/15"))
    )
    (comp (ref "R100")
      (value "3.3K")
      (footprint "eagle-import:0207_10")
      (libsource (lib "eagle-import") (part "R-US_0207/10"))
    )
    (comp (ref "R101")
      (value "3.3K")
      (footprint "eagle-import:0207_10")
      (libsource (lib "eagle-import") (part "R-US_0207/10"))
    )
    (comp (ref "R102")
      (value "2.2K")
      (footprint "eagle-import:0207_10")
      (libsource (lib "eagle-import") (part "R-US_0207/10"))
    )
    (comp (ref "R103")
      (value "243K")
      (footprint "eagle-import:0207_15")
      (libsource (lib "eagle-import") (part "R-US_0207/15"))
    )
    (comp (ref "R104")
      (value "256K")
      (footprint "eagle-import:0207_15")
      (libsource (lib "eagle-import") (part "R-US_0207/15"))
    )
    (comp (ref "R105")
      (value "3.3K")
      (footprint "eagle-import:0207_10")
      (libsource (lib "eagle-import") (part "R-US_0207/10"))
    )
    (comp (ref "R106")
      (value "121K")
      (footprint "eagle-import:0207_15")
      (libsource (lib "eagle-import") (part "R-US_0207/15"))
    )
    (comp (ref "R107")
      (value "128K")
      (footprint "eagle-import:0207_15")
      (libsource (lib "eagle-import") (part "R-US_0207/15"))
    )
    (comp (ref "R108")
      (value "3.3K")
      (footprint "eagle-import:0207_10")
      (libsource (lib "eagle-import") (part "R-US_0207/10"))
    )
    (comp (ref "R109")
      (value "68.1K")
      (footprint "eagle-import:0207_15")
      (libsource (lib "eagle-import") (part "R-US_0207/15"))
    )
    (comp (ref "R110")
      (value "64K")
      (footprint "eagle-import:0207_15")
      (libsource (lib "eagle-import") (part "R-US_0207/15"))
    )
    (comp (ref "R111")
      (value "3.3K")
      (footprint "eagle-import:0207_10")
      (libsource (lib "eagle-import") (part "R-US_0207/10"))
    )
    (comp (ref "R112")
      (value "31.6K")
      (footprint "eagle-import:0207_15")
      (libsource (lib "eagle-import") (part "R-US_0207/15"))
    )
    (comp (ref "R113")
      (value "32K")
      (footprint "eagle-import:0207_15")
      (libsource (lib "eagle-import") (part "R-US_0207/15"))
    )
    (comp (ref "R114")
      (value "3.3K")
      (footprint "eagle-import:0207_10")
      (libsource (lib "eagle-import") (part "R-US_0207/10"))
    )
    (comp (ref "R115")
      (value "14.7K")
      (footprint "eagle-import:0207_15")
      (libsource (lib "eagle-import") (part "R-US_0207/15"))
    )
    (comp (ref "R116")
      (value "500")
      (footprint "eagle-import:S75P")
      (libsource (lib "eagle-import") (part "TRIM_EU-S75P"))
    )
    (comp (ref "R117")
      (value "7.985K")
      (footprint "eagle-import:0207_15")
      (libsource (lib "eagle-import") (part "R-US_0207/15"))
    )
    (comp (ref "R118")
      (value "7.985K")
      (footprint "eagle-import:0207_15")
      (libsource (lib "eagle-import") (part "R-US_0207/15"))
    )
    (comp (ref "R119")
      (value "3.3K")
      (footprint "eagle-import:0207_10")
      (libsource (lib "eagle-import") (part "R-US_0207/10"))
    )
    (comp (ref "R120")
      (value "8.25K")
      (footprint "eagle-import:0207_15")
      (libsource (lib "eagle-import") (part "R-US_0207/15"))
    )
    (comp (ref "R121")
      (value "100")
      (footprint "eagle-import:S75P")
      (libsource (lib "eagle-import") (part "TRIM_EU-S75P"))
    )
    (comp (ref "R122")
      (value "7.985K")
      (footprint "eagle-import:0207_15")
      (libsource (lib "eagle-import") (part "R-US_0207/15"))
    )
    (comp (ref "R123")
      (value "3.3K")
      (footprint "eagle-import:0207_10")
      (libsource (lib "eagle-import") (part "R-US_0207/10"))
    )
    (comp (ref "R124")
      (value "3.83K")
      (footprint "eagle-import:0207_15")
      (libsource (lib "eagle-import") (part "R-US_0207/15"))
    )
    (comp (ref "R125")
      (value "50")
      (footprint "eagle-import:S75P")
      (libsource (lib "eagle-import") (part "TRIM_EU-S75P"))
    )
    (comp (ref "R126")
      (value "3.987K")
      (footprint "eagle-import:0207_15")
      (libsource (lib "eagle-import") (part "R-US_0207/15"))
    )
    (comp (ref "R127")
      (value "3.3K")
      (footprint "eagle-import:0207_10")
      (libsource (lib "eagle-import") (part "R-US_0207/10"))
    )
    (comp (ref "R128")
      (value "1.96K")
      (footprint "eagle-import:0207_15")
      (libsource (lib "eagle-import") (part "R-US_0207/15"))
    )
    (comp (ref "R129")
      (value "50")
      (footprint "eagle-import:S75P")
      (libsource (lib "eagle-import") (part "TRIM_EU-S75P"))
    )
    (comp (ref "R130")
      (value "1.992K")
      (footprint "eagle-import:0207_15")
      (libsource (lib "eagle-import") (part "R-US_0207/15"))
    )
    (comp (ref "R131")
      (value "3.3K")
      (footprint "eagle-import:0207_10")
      (libsource (lib "eagle-import") (part "R-US_0207/10"))
    )
    (comp (ref "R132")
      (value "1K")
      (footprint "eagle-import:0207_15")
      (libsource (lib "eagle-import") (part "R-US_0207/15"))
    )
    (comp (ref "R133")
      (value "20")
      (footprint "eagle-import:S75P")
      (libsource (lib "eagle-import") (part "TRIM_EU-S75P"))
    )
    (comp (ref "R134")
      (value "200K")
      (footprint "eagle-import:0207_15")
      (libsource (lib "eagle-import") (part "R-US_0207/15"))
    )
    (comp (ref "R135")
      (value "1K")
      (footprint "eagle-import:0207_15")
      (libsource (lib "eagle-import") (part "R-US_0207/15"))
    )
    (comp (ref "R136")
      (value "4.7K")
      (footprint "eagle-import:0207_10")
      (libsource (lib "eagle-import") (part "R-US_0207/10"))
    )
    (comp (ref "R137")
      (value "390")
      (footprint "eagle-import:0207_10")
      (libsource (lib "eagle-import") (part "R-US_0207/10"))
    )
    (comp (ref "R138")
      (value "18")
      (footprint "eagle-import:0207_10")
      (libsource (lib "eagle-import") (part "R-US_0207/10"))
    )
    (comp (ref "R139")
      (value "390")
      (footprint "eagle-import:0207_10")
      (libsource (lib "eagle-import") (part "R-US_0207/10"))
    )
    (comp (ref "R140")
      (value "18")
      (footprint "eagle-import:0207_10")
      (libsource (lib "eagle-import") (part "R-US_0207/10"))
    )
    (comp (ref "R141")
      (value "1K 1%")
      (footprint "eagle-import:0207_15")
      (libsource (lib "eagle-import") (part "R-US_0207/15"))
    )
    (comp (ref "R142")
      (value "10K")
      (footprint "eagle-import:0207_10")
      (libsource (lib "eagle-import") (part "R-US_0207/10"))
    )
    (comp (ref "R143")
      (value "47")
      (footprint "eagle-import:0207_10")
      (libsource (lib "eagle-import") (part "R-US_0207/10"))
    )
    (comp (ref "R144")
      (value "18")
      (footprint "eagle-import:0207_10")
      (libsource (lib "eagle-import") (part "R-US_0207/10"))
    )
    (comp (ref "R145")
      (value "4.7K")
      (footprint "eagle-import:0207_10")
      (libsource (lib "eagle-import") (part "R-US_0207/10"))
    )
    (comp (ref "R146")
      (value "390")
      (footprint "eagle-import:0207_10")
      (libsource (lib "eagle-import") (part "R-US_0207/10"))
    )
    (comp (ref "R147")
      (value "18")
      (footprint "eagle-import:0207_10")
      (libsource (lib "eagle-import") (part "R-US_0207/10"))
    )
    (comp (ref "R148")
      (value "133")
      (footprint "eagle-import:0207_15")
      (libsource (lib "eagle-import") (part "R-US_0207/15"))
    )
    (comp (ref "R149")
      (value "866 1%")
      (footprint "eagle-import:0207_15")
      (libsource (lib "eagle-import") (part "R-US_0207/15"))
    )
    (comp (ref "TP1")
      (value "TPSQPAD1-17")
      (footprint "eagle-import:P1-17")
      (libsource (lib "eagle-import") (part "TPSQPAD1-17"))
    )
    (comp (ref "TP2")
      (value "TPSQPAD1-17")
      (footprint "eagle-import:P1-17")
      (libsource (lib "eagle-import") (part "TPSQPAD1-17"))
    )
    (comp (ref "W1")
      (value "0")
      (footprint "eagle-import:0207_10")
      (libsource (lib "eagle-import") (part "R-EU_0207/10"))
    )
    (comp (ref "W2")
      (value "open")
      (footprint "eagle-import:0207_10")
      (libsource (lib "eagle-import") (part "R-EU_0207/10"))
    )
    (comp (ref "W3")
      (value "open")
      (footprint "eagle-import:0207_10")
      (libsource (lib "eagle-import") (part "R-EU_0207/10"))
    )
    (comp (ref "W4")
      (value "OPEN")
      (footprint "eagle-import:0207_10")
      (libsource (lib "eagle-import") (part "R-EU_0207/10"))
    )
    (comp (ref "W5")
      (value "OPEN")
      (footprint "eagle-import:0207_10")
      (libsource (lib "eagle-import") (part "R-EU_0207/10"))
    )
    (comp (ref "W6")
      (value "OPEN")
      (footprint "eagle-import:0207_10")
      (libsource (lib "eagle-import") (part "R-EU_0207/10"))
    )
  )
  (nets
    (net (code "1") (name "+15V") (class "Default")
      (node (ref "D24") (pin "C") (pinfunction "C_C") (pintype "passive"))
      (node (ref "E14") (pin "7") (pinfunction "V+_7") (pintype "power_in"))
      (node (ref "E15") (pin "7") (pinfunction "V+_7") (pintype "power_in"))
      (node (ref "F") (pin "D1") (pinfunction "P_D1") (pintype "passive"))
      (node (ref "F") (pin "E1") (pinfunction "P_E1") (pintype "passive"))
      (node (ref "H") (pin "R1") (pinfunction "P_R1") (pintype "passive"))
      (node (ref "H") (pin "S1") (pinfunction "P_S1") (pintype "passive"))
      (node (ref "R103") (pin "2") (pinfunction "2_2") (pintype "passive"))
      (node (ref "R106") (pin "2") (pinfunction "2_2") (pintype "passive"))
      (node (ref "R109") (pin "2") (pinfunction "2_2") (pintype "passive"))
      (node (ref "R11") (pin "2") (pinfunction "2_2") (pintype "passive"))
      (node (ref "R112") (pin "2") (pinfunction "2_2") (pintype "passive"))
      (node (ref "R115") (pin "2") (pinfunction "2_2") (pintype "passive"))
      (node (ref "R120") (pin "2") (pinfunction "2_2") (pintype "passive"))
      (node (ref "R124") (pin "2") (pinfunction "2_2") (pintype "passive"))
      (node (ref "R128") (pin "2") (pinfunction "2_2") (pintype "passive"))
      (node (ref "R132") (pin "2") (pinfunction "2_2") (pintype "passive"))
      (node (ref "R138") (pin "2") (pinfunction "2_2") (pintype "passive"))
      (node (ref "R16") (pin "2") (pinfunction "2_2") (pintype "passive"))
      (node (ref "R19") (pin "2") (pinfunction "2_2") (pintype "passive"))
      (node (ref "R22") (pin "2") (pinfunction "2_2") (pintype "passive"))
      (node (ref "R25") (pin "2") (pinfunction "2_2") (pintype "passive"))
      (node (ref "R28") (pin "2") (pinfunction "2_2") (pintype "passive"))
      (node (ref "R33") (pin "2") (pinfunction "2_2") (pintype "passive"))
      (node (ref "R37") (pin "2") (pinfunction "2_2") (pintype "passive"))
      (node (ref "R41") (pin "2") (pinfunction "2_2") (pintype "passive"))
      (node (ref "R45") (pin "2") (pinfunction "2_2") (pintype "passive"))
      (node (ref "R51") (pin "2") (pinfunction "2_2") (pintype "passive"))
      (node (ref "R68") (pin "2") (pinfunction "2_2") (pintype "passive"))
      (node (ref "R98") (pin "2") (pinfunction "2_2") (pintype "passive"))
    )
    (net (code "2") (name "-15V") (class "Default")
      (node (ref "C15") (pin "-") (pinfunction "-_-") (pintype "passive"))
      (node (ref "C17") (pin "-") (pinfunction "-_-") (pintype "passive"))
      (node (ref "C19") (pin "-") (pinfunction "-_-") (pintype "passive"))
      (node (ref "C21") (pin "-") (pinfunction "-_-") (pintype "passive"))
      (node (ref "D29") (pin "A") (pinfunction "A_A") (pintype "passive"))
      (node (ref "F") (pin "F1") (pinfunction "P_F1") (pintype "passive"))
      (node (ref "F") (pin "H1") (pinfunction "P_H1") (pintype "passive"))
      (node (ref "H") (pin "N1") (pinfunction "P_N1") (pintype "passive"))
      (node (ref "H") (pin "P1") (pinfunction "P_P1") (pintype "passive"))
      (node (ref "OMNIBUS") (pin "AB2") (pinfunction "1_AB2") (pintype "bidirectional"))
      (node (ref "OMNIBUS") (pin "BB2") (pinfunction "1_BB2") (pintype "bidirectional"))
      (node (ref "OMNIBUS") (pin "CB2") (pinfunction "1_CB2") (pintype "bidirectional"))
      (node (ref "R147") (pin "1") (pinfunction "1_1") (pintype "passive"))
      (node (ref "R80") (pin "1") (pinfunction "1_1") (pintype "passive"))
      (node (ref "R90") (pin "1") (pinfunction "1_1") (pintype "passive"))
      (node (ref "R91") (pin "1") (pinfunction "1_1") (pintype "passive"))
    )
    (net (code "3") (name "/+5V_X") (class "Default")
      (node (ref "D11") (pin "C") (pinfunction "C_C") (pintype "passive"))
      (node (ref "D13") (pin "C") (pinfunction "C_C") (pintype "passive"))
      (node (ref "D15") (pin "C") (pinfunction "C_C") (pintype "passive"))
      (node (ref "D17") (pin "C") (pinfunction "C_C") (pintype "passive"))
      (node (ref "D19") (pin "C") (pinfunction "C_C") (pintype "passive"))
      (node (ref "D21") (pin "C") (pinfunction "C_C") (pintype "passive"))
      (node (ref "D3") (pin "C") (pinfunction "C_C") (pintype "passive"))
      (node (ref "D6") (pin "C") (pinfunction "C_C") (pintype "passive"))
      (node (ref "D7") (pin "C") (pinfunction "C_C") (pintype "passive"))
      (node (ref "D9") (pin "C") (pinfunction "C_C") (pintype "passive"))
      (node (ref "E14") (pin "6") (pinfunction "OUT_6") (pintype "output"))
      (node (ref "J1") (pin "UU") (pinfunction "39_UU") (pintype "bidirectional"))
      (node (ref "R49") (pin "2") (pinfunction "2_2") (pintype "passive"))
    )
    (net (code "4") (name "/+5V_Y") (class "Default")
      (node (ref "D32") (pin "C") (pinfunction "C_C") (pintype "passive"))
      (node (ref "D35") (pin "C") (pinfunction "C_C") (pintype "passive"))
      (node (ref "D36") (pin "C") (pinfunction "C_C") (pintype "passive"))
      (node (ref "D38") (pin "C") (pinfunction "C_C") (pintype "passive"))
      (node (ref "D40") (pin "C") (pinfunction "C_C") (pintype "passive"))
      (node (ref "D42") (pin "C") (pinfunction "C_C") (pintype "passive"))
      (node (ref "D44") (pin "C") (pinfunction "C_C") (pintype "passive"))
      (node (ref "D46") (pin "C") (pinfunction "C_C") (pintype "passive"))
      (node (ref "D48") (pin "C") (pinfunction "C_C") (pintype "passive"))
      (node (ref "D50") (pin "C") (pinfunction "C_C") (pintype "passive"))
      (node (ref "E15") (pin "6") (pinfunction "OUT_6") (pintype "output"))
      (node (ref "J1") (pin "SS") (pinfunction "37_SS") (pintype "bidirectional"))
      (node (ref "R54") (pin "2") (pinfunction "2_2") (pintype "passive"))
    )
    (net (code "5") (name "/BIT10") (class "Default")
      (node (ref "E7") (pin "1") (pinfunction "B_1") (pintype "input"))
      (node (ref "E8") (pin "1") (pinfunction "B_1") (pintype "input"))
      (node (ref "F") (pin "U1") (pinfunction "P_U1") (pintype "passive"))
    )
    (net (code "6") (name "/BIT11") (class "Default")
      (node (ref "E7") (pin "15") (pinfunction "A_15") (pintype "input"))
      (node (ref "E8") (pin "15") (pinfunction "A_15") (pintype "input"))
      (node (ref "F") (pin "T1") (pinfunction "P_T1") (pintype "passive"))
    )
    (net (code "7") (name "/CLEAR") (class "Default")
      (node (ref "F") (pin "N1") (pinfunction "P_N1") (pintype "passive"))
      (node (ref "H") (pin "H1") (pinfunction "P_H1") (pintype "passive"))
    )
    (net (code "8") (name "/DI02") (class "Default")
      (node (ref "E1") (pin "1") (pinfunction "B_1") (pintype "input"))
      (node (ref "E2") (pin "1") (pinfunction "B_1") (pintype "input"))
      (node (ref "E3") (pin "2") (pinfunction "O_2") (pintype "output"))
    )
    (net (code "9") (name "/DI03") (class "Default")
      (node (ref "E1") (pin "15") (pinfunction "A_15") (pintype "input"))
      (node (ref "E2") (pin "15") (pinfunction "A_15") (pintype "input"))
      (node (ref "E3") (pin "3") (pinfunction "O_3") (pintype "output"))
    )
    (net (code "10") (name "/DI04") (class "Default")
      (node (ref "E4") (pin "9") (pinfunction "D_9") (pintype "input"))
      (node (ref "E5") (pin "9") (pinfunction "D_9") (pintype "input"))
      (node (ref "E6") (pin "3") (pinfunction "O_3") (pintype "output"))
    )
    (net (code "11") (name "/DI05") (class "Default")
      (node (ref "E4") (pin "10") (pinfunction "C_10") (pintype "input"))
      (node (ref "E5") (pin "10") (pinfunction "C_10") (pintype "input"))
      (node (ref "E6") (pin "2") (pinfunction "O_2") (pintype "output"))
    )
    (net (code "12") (name "/DI06") (class "Default")
      (node (ref "E4") (pin "1") (pinfunction "B_1") (pintype "input"))
      (node (ref "E5") (pin "1") (pinfunction "B_1") (pintype "input"))
      (node (ref "E6") (pin "14") (pinfunction "O_14") (pintype "output"))
    )
    (net (code "13") (name "/DI07") (class "Default")
      (node (ref "E4") (pin "15") (pinfunction "A_15") (pintype "input"))
      (node (ref "E5") (pin "15") (pinfunction "A_15") (pintype "input"))
      (node (ref "E6") (pin "13") (pinfunction "O_13") (pintype "output"))
    )
    (net (code "14") (name "/DI08") (class "Default")
      (node (ref "E3") (pin "13") (pinfunction "O_13") (pintype "output"))
      (node (ref "E7") (pin "9") (pinfunction "D_9") (pintype "input"))
      (node (ref "E8") (pin "9") (pinfunction "D_9") (pintype "input"))
    )
    (net (code "15") (name "/DI09") (class "Default")
      (node (ref "E3") (pin "14") (pinfunction "O_14") (pintype "output"))
      (node (ref "E7") (pin "10") (pinfunction "C_10") (pintype "input"))
      (node (ref "E8") (pin "10") (pinfunction "C_10") (pintype "input"))
    )
    (net (code "16") (name "/EX_ANALOG_X") (class "Default")
      (node (ref "H") (pin "B2") (pinfunction "P_B2") (pintype "passive"))
      (node (ref "R81") (pin "2") (pinfunction "2_2") (pintype "passive"))
    )
    (net (code "17") (name "/EX_ANALOG_Y") (class "Default")
      (node (ref "H") (pin "C2") (pinfunction "P_C2") (pintype "passive"))
      (node (ref "R93") (pin "2") (pinfunction "2_2") (pintype "passive"))
    )
    (net (code "18") (name "/INTENS") (class "Default")
      (node (ref "C22") (pin "1") (pinfunction "1_1") (pintype "passive"))
      (node (ref "F") (pin "S1") (pinfunction "P_S1") (pintype "passive"))
      (node (ref "H") (pin "D1") (pinfunction "P_D1") (pintype "passive"))
      (node (ref "R56") (pin "1") (pinfunction "1_1") (pintype "passive"))
      (node (ref "R57") (pin "1") (pinfunction "1_1") (pintype "passive"))
    )
    (net (code "19") (name "/LOAD_X") (class "Default")
      (node (ref "E2") (pin "11") (pinfunction "LD_11") (pintype "input"))
      (node (ref "E5") (pin "11") (pinfunction "LD_11") (pintype "input"))
      (node (ref "E8") (pin "11") (pinfunction "LD_11") (pintype "input"))
      (node (ref "F") (pin "V2") (pinfunction "P_V2") (pintype "passive"))
    )
    (net (code "20") (name "/LOAD_Y") (class "Default")
      (node (ref "E1") (pin "11") (pinfunction "LD_11") (pintype "input"))
      (node (ref "E4") (pin "11") (pinfunction "LD_11") (pintype "input"))
      (node (ref "E7") (pin "11") (pinfunction "LD_11") (pintype "input"))
      (node (ref "F") (pin "U2") (pinfunction "P_U2") (pintype "passive"))
    )
    (net (code "21") (name "/X02") (class "Default")
      (node (ref "E12") (pin "1") (pinfunction "I_1") (pintype "input"))
      (node (ref "E13") (pin "6") (pinfunction "A1_6") (pintype "input"))
      (node (ref "E2") (pin "2") (pinfunction "QB_2") (pintype "output"))
    )
    (net (code "22") (name "/X03") (class "Default")
      (node (ref "E13") (pin "1") (pinfunction "A0_1") (pintype "input"))
      (node (ref "E2") (pin "3") (pinfunction "QA_3") (pintype "output"))
      (node (ref "R40") (pin "1") (pinfunction "1_1") (pintype "passive"))
    )
    (net (code "23") (name "/X04") (class "Default")
      (node (ref "E11") (pin "15") (pinfunction "A3_15") (pintype "input"))
      (node (ref "E5") (pin "7") (pinfunction "QD_7") (pintype "output"))
      (node (ref "R36") (pin "1") (pinfunction "1_1") (pintype "passive"))
    )
    (net (code "24") (name "/X05") (class "Default")
      (node (ref "E11") (pin "10") (pinfunction "A2_10") (pintype "input"))
      (node (ref "E5") (pin "6") (pinfunction "QC_6") (pintype "output"))
      (node (ref "R32") (pin "1") (pinfunction "1_1") (pintype "passive"))
    )
    (net (code "25") (name "/X06") (class "Default")
      (node (ref "E11") (pin "6") (pinfunction "A1_6") (pintype "input"))
      (node (ref "E5") (pin "2") (pinfunction "QB_2") (pintype "output"))
      (node (ref "R27") (pin "1") (pinfunction "1_1") (pintype "passive"))
    )
    (net (code "26") (name "/X07") (class "Default")
      (node (ref "E11") (pin "1") (pinfunction "A0_1") (pintype "input"))
      (node (ref "E5") (pin "3") (pinfunction "QA_3") (pintype "output"))
      (node (ref "R24") (pin "1") (pinfunction "1_1") (pintype "passive"))
    )
    (net (code "27") (name "/X08") (class "Default")
      (node (ref "E8") (pin "7") (pinfunction "QD_7") (pintype "output"))
      (node (ref "E9") (pin "15") (pinfunction "A3_15") (pintype "input"))
      (node (ref "R21") (pin "1") (pinfunction "1_1") (pintype "passive"))
    )
    (net (code "28") (name "/X09") (class "Default")
      (node (ref "E8") (pin "6") (pinfunction "QC_6") (pintype "output"))
      (node (ref "E9") (pin "10") (pinfunction "A2_10") (pintype "input"))
      (node (ref "R18") (pin "1") (pinfunction "1_1") (pintype "passive"))
    )
    (net (code "29") (name "/X10") (class "Default")
      (node (ref "E8") (pin "2") (pinfunction "QB_2") (pintype "output"))
      (node (ref "E9") (pin "6") (pinfunction "A1_6") (pintype "input"))
      (node (ref "R13") (pin "1") (pinfunction "1_1") (pintype "passive"))
    )
    (net (code "30") (name "/X11") (class "Default")
      (node (ref "E8") (pin "3") (pinfunction "QA_3") (pintype "output"))
      (node (ref "E9") (pin "1") (pinfunction "A0_1") (pintype "input"))
      (node (ref "R8") (pin "1") (pinfunction "1_1") (pintype "passive"))
    )
    (net (code "31") (name "/X_ANALOG") (class "Default")
      (node (ref "H") (pin "C1") (pinfunction "P_C1") (pintype "passive"))
      (node (ref "J1") (pin "D") (pinfunction "4_D") (pintype "bidirectional"))
      (node (ref "R73") (pin "2") (pinfunction "2_2") (pintype "passive"))
    )
    (net (code "32") (name "/X_DEC") (class "Default")
      (node (ref "E8") (pin "4") (pinfunction "DN_4") (pintype "input"))
      (node (ref "H") (pin "H2") (pinfunction "P_H2") (pintype "passive"))
      (node (ref "R3") (pin "1") (pinfunction "1_1") (pintype "passive"))
    )
    (net (code "33") (name "/X_INC") (class "Default")
      (node (ref "E8") (pin "5") (pinfunction "UP_5") (pintype "input"))
      (node (ref "H") (pin "E2") (pinfunction "P_E2") (pintype "passive"))
      (node (ref "R2") (pin "1") (pinfunction "1_1") (pintype "passive"))
    )
    (net (code "34") (name "/Y02") (class "Default")
      (node (ref "E1") (pin "2") (pinfunction "QB_2") (pintype "output"))
      (node (ref "E12") (pin "13") (pinfunction "I_13") (pintype "input"))
      (node (ref "E12") (pin "3") (pinfunction "I_3") (pintype "input"))
    )
    (net (code "35") (name "/Y03") (class "Default")
      (node (ref "E1") (pin "3") (pinfunction "QA_3") (pintype "output"))
      (node (ref "E12") (pin "5") (pinfunction "I_5") (pintype "input"))
      (node (ref "R127") (pin "1") (pinfunction "1_1") (pintype "passive"))
    )
    (net (code "36") (name "/Y04") (class "Default")
      (node (ref "E10") (pin "9") (pinfunction "I_9") (pintype "input"))
      (node (ref "E4") (pin "7") (pinfunction "QD_7") (pintype "output"))
      (node (ref "R123") (pin "1") (pinfunction "1_1") (pintype "passive"))
    )
    (net (code "37") (name "/Y05") (class "Default")
      (node (ref "E10") (pin "11") (pinfunction "I_11") (pintype "input"))
      (node (ref "E4") (pin "6") (pinfunction "QC_6") (pintype "output"))
      (node (ref "R119") (pin "1") (pinfunction "1_1") (pintype "passive"))
    )
    (net (code "38") (name "/Y06") (class "Default")
      (node (ref "E10") (pin "3") (pinfunction "I_3") (pintype "input"))
      (node (ref "E4") (pin "2") (pinfunction "QB_2") (pintype "output"))
      (node (ref "R114") (pin "1") (pinfunction "1_1") (pintype "passive"))
    )
    (net (code "39") (name "/Y07") (class "Default")
      (node (ref "E10") (pin "5") (pinfunction "I_5") (pintype "input"))
      (node (ref "E4") (pin "3") (pinfunction "QA_3") (pintype "output"))
      (node (ref "R111") (pin "1") (pinfunction "1_1") (pintype "passive"))
    )
    (net (code "40") (name "/Y08") (class "Default")
      (node (ref "E10") (pin "1") (pinfunction "I_1") (pintype "input"))
      (node (ref "E7") (pin "7") (pinfunction "QD_7") (pintype "output"))
      (node (ref "R108") (pin "1") (pinfunction "1_1") (pintype "passive"))
    )
    (net (code "41") (name "/Y09") (class "Default")
      (node (ref "E10") (pin "13") (pinfunction "I_13") (pintype "input"))
      (node (ref "E7") (pin "6") (pinfunction "QC_6") (pintype "output"))
      (node (ref "R105") (pin "1") (pinfunction "1_1") (pintype "passive"))
    )
    (net (code "42") (name "/Y10") (class "Default")
      (node (ref "E12") (pin "9") (pinfunction "I_9") (pintype "input"))
      (node (ref "E7") (pin "2") (pinfunction "QB_2") (pintype "output"))
      (node (ref "R100") (pin "1") (pinfunction "1_1") (pintype "passive"))
    )
    (net (code "43") (name "/Y11") (class "Default")
      (node (ref "E12") (pin "11") (pinfunction "I_11") (pintype "input"))
      (node (ref "E7") (pin "3") (pinfunction "QA_3") (pintype "output"))
      (node (ref "R95") (pin "1") (pinfunction "1_1") (pintype "passive"))
    )
    (net (code "44") (name "/Y_ANALOG") (class "Default")
      (node (ref "H") (pin "A1") (pinfunction "P_A1") (pintype "passive"))
      (node (ref "J1") (pin "L") (pinfunction "10_L") (pintype "bidirectional"))
      (node (ref "R143") (pin "2") (pinfunction "2_2") (pintype "passive"))
    )
    (net (code "45") (name "/Y_DEC") (class "Default")
      (node (ref "E7") (pin "4") (pinfunction "DN_4") (pintype "input"))
      (node (ref "H") (pin "J2") (pinfunction "P_J2") (pintype "passive"))
      (node (ref "R6") (pin "1") (pinfunction "1_1") (pintype "passive"))
    )
    (net (code "46") (name "/Y_INC") (class "Default")
      (node (ref "E7") (pin "5") (pinfunction "UP_5") (pintype "input"))
      (node (ref "H") (pin "F2") (pinfunction "P_F2") (pintype "passive"))
      (node (ref "R5") (pin "1") (pinfunction "1_1") (pintype "passive"))
    )
    (net (code "47") (name "/Z_AXIS") (class "Default")
      (node (ref "J1") (pin "X") (pinfunction "20_X") (pintype "bidirectional"))
      (node (ref "R65") (pin "2") (pinfunction "2_2") (pintype "passive"))
    )
    (net (code "48") (name "/Z_PULSE") (class "Default")
      (node (ref "F") (pin "A2") (pinfunction "P_A2") (pintype "passive"))
      (node (ref "H") (pin "V2") (pinfunction "P_V2") (pintype "passive"))
    )
    (net (code "49") (name "/~{CHAN}") (class "Default")
      (node (ref "F") (pin "R1") (pinfunction "P_R1") (pintype "passive"))
      (node (ref "H") (pin "E1") (pinfunction "P_E1") (pintype "passive"))
      (node (ref "J1") (pin "Z") (pinfunction "22_Z") (pintype "bidirectional"))
    )
    (net (code "50") (name "/~{COL_RED}") (class "Default")
      (node (ref "F") (pin "L1") (pinfunction "P_L1") (pintype "passive"))
      (node (ref "J1") (pin "DD") (pinfunction "26_DD") (pintype "bidirectional"))
    )
    (net (code "51") (name "/~{DATA02}") (class "Default")
      (node (ref "E13") (pin "4") (pinfunction "F1_4") (pintype "open_collector"))
      (node (ref "E3") (pin "7") (pinfunction "I1_7") (pintype "input"))
      (node (ref "OMNIBUS") (pin "AU1") (pinfunction "1_AU1") (pintype "bidirectional"))
    )
    (net (code "52") (name "/~{DATA03}") (class "Default")
      (node (ref "E13") (pin "3") (pinfunction "F0_3") (pintype "open_collector"))
      (node (ref "E3") (pin "4") (pinfunction "I0_4") (pintype "input"))
      (node (ref "OMNIBUS") (pin "AV1") (pinfunction "1_AV1") (pintype "bidirectional"))
    )
    (net (code "53") (name "/~{DATA04}") (class "Default")
      (node (ref "E11") (pin "13") (pinfunction "F3_13") (pintype "open_collector"))
      (node (ref "E6") (pin "4") (pinfunction "I0_4") (pintype "input"))
      (node (ref "OMNIBUS") (pin "BR1") (pinfunction "1_BR1") (pintype "bidirectional"))
    )
    (net (code "54") (name "/~{DATA05}") (class "Default")
      (node (ref "E11") (pin "12") (pinfunction "F2_12") (pintype "open_collector"))
      (node (ref "E6") (pin "7") (pinfunction "I1_7") (pintype "input"))
      (node (ref "OMNIBUS") (pin "BS1") (pinfunction "1_BS1") (pintype "bidirectional"))
    )
    (net (code "55") (name "/~{DATA06}") (class "Default")
      (node (ref "E11") (pin "4") (pinfunction "F1_4") (pintype "open_collector"))
      (node (ref "E6") (pin "10") (pinfunction "I1_10") (pintype "input"))
      (node (ref "OMNIBUS") (pin "BU1") (pinfunction "1_BU1") (pintype "bidirectional"))
    )
    (net (code "56") (name "/~{DATA07}") (class "Default")
      (node (ref "E11") (pin "3") (pinfunction "F0_3") (pintype "open_collector"))
      (node (ref "E6") (pin "12") (pinfunction "I1_12") (pintype "input"))
      (node (ref "OMNIBUS") (pin "BV1") (pinfunction "1_BV1") (pintype "bidirectional"))
    )
    (net (code "57") (name "/~{DATA08}") (class "Default")
      (node (ref "E3") (pin "12") (pinfunction "I1_12") (pintype "input"))
      (node (ref "E9") (pin "13") (pinfunction "F3_13") (pintype "open_collector"))
      (node (ref "OMNIBUS") (pin "DR1") (pinfunction "1_DR1") (pintype "bidirectional"))
    )
    (net (code "58") (name "/~{DATA09}") (class "Default")
      (node (ref "E3") (pin "9") (pinfunction "I0_9") (pintype "input"))
      (node (ref "E9") (pin "12") (pinfunction "F2_12") (pintype "open_collector"))
      (node (ref "OMNIBUS") (pin "DS1") (pinfunction "1_DS1") (pintype "bidirectional"))
    )
    (net (code "59") (name "/~{DATA10}") (class "Default")
      (node (ref "E9") (pin "3") (pinfunction "F0_3") (pintype "open_collector"))
      (node (ref "OMNIBUS") (pin "DU1") (pinfunction "1_DU1") (pintype "bidirectional"))
    )
    (net (code "60") (name "/~{DATA11}") (class "Default")
      (node (ref "E9") (pin "4") (pinfunction "F1_4") (pintype "open_collector"))
      (node (ref "OMNIBUS") (pin "DV1") (pinfunction "1_DV1") (pintype "bidirectional"))
    )
    (net (code "61") (name "/~{DILE}") (class "Default")
      (node (ref "F") (pin "P1") (pinfunction "P_P1") (pintype "passive"))
      (node (ref "H") (pin "F1") (pinfunction "P_F1") (pintype "passive"))
    )
    (net (code "62") (name "/~{DIRE}") (class "Default")
      (node (ref "F") (pin "B2") (pinfunction "P_B2") (pintype "passive"))
      (node (ref "H") (pin "U2") (pinfunction "P_U2") (pintype "passive"))
    )
    (net (code "63") (name "/~{ERASE_INTERVAL}") (class "Default")
      (node (ref "F") (pin "D2") (pinfunction "P_D2") (pintype "passive"))
      (node (ref "J1") (pin "NN") (pinfunction "34_NN") (pintype "bidirectional"))
    )
    (net (code "64") (name "/~{ERASE}") (class "Default")
      (node (ref "F") (pin "K1") (pinfunction "P_K1") (pintype "passive"))
      (node (ref "J1") (pin "FF") (pinfunction "28_FF") (pintype "bidirectional"))
    )
    (net (code "65") (name "/~{LOAD_EN}") (class "Default")
      (node (ref "E3") (pin "10") (pinfunction "I1_10") (pintype "input"))
      (node (ref "E3") (pin "11") (pinfunction "I0_11") (pintype "input"))
      (node (ref "E3") (pin "5") (pinfunction "I1_5") (pintype "input"))
      (node (ref "E3") (pin "6") (pinfunction "I0_6") (pintype "input"))
      (node (ref "E6") (pin "11") (pinfunction "I0_11") (pintype "input"))
      (node (ref "E6") (pin "5") (pinfunction "I1_5") (pintype "input"))
      (node (ref "E6") (pin "6") (pinfunction "I0_6") (pintype "input"))
      (node (ref "E6") (pin "9") (pinfunction "I0_9") (pintype "input"))
      (node (ref "F") (pin "V1") (pinfunction "P_V1") (pintype "passive"))
      (node (ref "R1") (pin "1") (pinfunction "1_1") (pintype "passive"))
    )
    (net (code "66") (name "/~{NON_STORE}") (class "Default")
      (node (ref "F") (pin "C2") (pinfunction "P_C2") (pintype "passive"))
      (node (ref "J1") (pin "LL") (pinfunction "32_LL") (pintype "bidirectional"))
    )
    (net (code "67") (name "/~{WRITE_THRU}") (class "Default")
      (node (ref "F") (pin "M1") (pinfunction "P_M1") (pintype "passive"))
      (node (ref "J1") (pin "JJ") (pinfunction "30_JJ") (pintype "bidirectional"))
    )
    (net (code "68") (name "/~{X_AC}") (class "Default")
      (node (ref "E11") (pin "7") (pinfunction "S1_7") (pintype "input"))
      (node (ref "E13") (pin "7") (pinfunction "S1_7") (pintype "input"))
      (node (ref "E9") (pin "7") (pinfunction "S1_7") (pintype "input"))
      (node (ref "H") (pin "K2") (pinfunction "P_K2") (pintype "passive"))
      (node (ref "R7") (pin "1") (pinfunction "1_1") (pintype "passive"))
    )
    (net (code "69") (name "/~{Y_AC}") (class "Default")
      (node (ref "E11") (pin "9") (pinfunction "S0_9") (pintype "input"))
      (node (ref "E13") (pin "9") (pinfunction "S0_9") (pintype "input"))
      (node (ref "E9") (pin "9") (pinfunction "S0_9") (pintype "input"))
      (node (ref "H") (pin "L2") (pinfunction "P_L2") (pintype "passive"))
      (node (ref "R4") (pin "1") (pinfunction "1_1") (pintype "passive"))
    )
    (net (code "70") (name "GND") (class "Default")
      (node (ref "C1") (pin "2") (pinfunction "2_2") (pintype "passive"))
      (node (ref "C10") (pin "2") (pinfunction "2_2") (pintype "passive"))
      (node (ref "C11") (pin "2") (pinfunction "2_2") (pintype "passive"))
      (node (ref "C12") (pin "2") (pinfunction "2_2") (pintype "passive"))
      (node (ref "C13") (pin "2") (pinfunction "2_2") (pintype "passive"))
      (node (ref "C14") (pin "-") (pinfunction "-_-") (pintype "passive"))
      (node (ref "C15") (pin "+") (pinfunction "+_+") (pintype "passive"))
      (node (ref "C16") (pin "-") (pinfunction "-_-") (pintype "passive"))
      (node (ref "C17") (pin "+") (pinfunction "+_+") (pintype "passive"))
      (node (ref "C18") (pin "-") (pinfunction "-_-") (pintype "passive"))
      (node (ref "C19") (pin "+") (pinfunction "+_+") (pintype "passive"))
      (node (ref "C2") (pin "2") (pinfunction "2_2") (pintype "passive"))
      (node (ref "C21") (pin "+") (pinfunction "+_+") (pintype "passive"))
      (node (ref "C23") (pin "2") (pinfunction "2_2") (pintype "passive"))
      (node (ref "C24") (pin "2") (pinfunction "2_2") (pintype "passive"))
      (node (ref "C26") (pin "-") (pinfunction "-_-") (pintype "passive"))
      (node (ref "C29") (pin "2") (pinfunction "2_2") (pintype "passive"))
      (node (ref "C3") (pin "2") (pinfunction "2_2") (pintype "passive"))
      (node (ref "C30") (pin "-") (pinfunction "-_-") (pintype "passive"))
      (node (ref "C31") (pin "1") (pinfunction "1_1") (pintype "passive"))
      (node (ref "C32") (pin "+") (pinfunction "+_+") (pintype "passive"))
      (node (ref "C33") (pin "2") (pinfunction "2_2") (pintype "passive"))
      (node (ref "C35") (pin "2") (pinfunction "2_2") (pintype "passive"))
      (node (ref "C37") (pin "2") (pinfunction "2_2") (pintype "passive"))
      (node (ref "C38") (pin "-") (pinfunction "-_-") (pintype "passive"))
      (node (ref "C39") (pin "1") (pinfunction "1_1") (pintype "passive"))
      (node (ref "C4") (pin "2") (pinfunction "2_2") (pintype "passive"))
      (node (ref "C40") (pin "+") (pinfunction "+_+") (pintype "passive"))
      (node (ref "C5") (pin "2") (pinfunction "2_2") (pintype "passive"))
      (node (ref "C6") (pin "2") (pinfunction "2_2") (pintype "passive"))
      (node (ref "C7") (pin "2") (pinfunction "2_2") (pintype "passive"))
      (node (ref "C8") (pin "2") (pinfunction "2_2") (pintype "passive"))
      (node (ref "C9") (pin "2") (pinfunction "2_2") (pintype "passive"))
      (node (ref "D23") (pin "A") (pinfunction "A_A") (pintype "passive"))
      (node (ref "D27") (pin "C") (pinfunction "C_C") (pintype "passive"))
      (node (ref "D28") (pin "C") (pinfunction "C_C") (pintype "passive"))
      (node (ref "D55") (pin "C") (pinfunction "C_C") (pintype "passive"))
      (node (ref "D57") (pin "C") (pinfunction "C_C") (pintype "passive"))
      (node (ref "E1") (pin "10") (pinfunction "C_10") (pintype "input"))
      (node (ref "E1") (pin "14") (pinfunction "CLR_14") (pintype "input"))
      (node (ref "E1") (pin "9") (pinfunction "D_9") (pintype "input"))
      (node (ref "E14") (pin "4") (pinfunction "V-_4") (pintype "power_in"))
      (node (ref "E15") (pin "4") (pinfunction "V-_4") (pintype "power_in"))
      (node (ref "E2") (pin "10") (pinfunction "C_10") (pintype "input"))
      (node (ref "E2") (pin "14") (pinfunction "CLR_14") (pintype "input"))
      (node (ref "E2") (pin "9") (pinfunction "D_9") (pintype "input"))
      (node (ref "E4") (pin "14") (pinfunction "CLR_14") (pintype "input"))
      (node (ref "E5") (pin "14") (pinfunction "CLR_14") (pintype "input"))
      (node (ref "E7") (pin "14") (pinfunction "CLR_14") (pintype "input"))
      (node (ref "E8") (pin "14") (pinfunction "CLR_14") (pintype "input"))
      (node (ref "F") (pin "A1") (pinfunction "P_A1") (pintype "passive"))
      (node (ref "F") (pin "B1") (pinfunction "P_B1") (pintype "passive"))
      (node (ref "F") (pin "C1") (pinfunction "P_C1") (pintype "passive"))
      (node (ref "H") (pin "T1") (pinfunction "P_T1") (pintype "passive"))
      (node (ref "H") (pin "U1") (pinfunction "P_U1") (pintype "passive"))
      (node (ref "H") (pin "V1") (pinfunction "P_V1") (pintype "passive"))
      (node (ref "J1") (pin "A") (pinfunction "1_A") (pintype "bidirectional"))
      (node (ref "J1") (pin "AA") (pinfunction "23_AA") (pintype "bidirectional"))
      (node (ref "J1") (pin "BB") (pinfunction "24_BB") (pintype "bidirectional"))
      (node (ref "J1") (pin "C") (pinfunction "3_C") (pintype "bidirectional"))
      (node (ref "J1") (pin "CC") (pinfunction "25_CC") (pintype "bidirectional"))
      (node (ref "J1") (pin "E") (pinfunction "5_E") (pintype "bidirectional"))
      (node (ref "J1") (pin "EE") (pinfunction "27_EE") (pintype "bidirectional"))
      (node (ref "J1") (pin "F") (pinfunction "6_F") (pintype "bidirectional"))
      (node (ref "J1") (pin "H") (pinfunction "7_H") (pintype "bidirectional"))
      (node (ref "J1") (pin "HH") (pinfunction "29_HH") (pintype "bidirectional"))
      (node (ref "J1") (pin "J") (pinfunction "8_J") (pintype "bidirectional"))
      (node (ref "J1") (pin "K") (pinfunction "9_K") (pintype "bidirectional"))
      (node (ref "J1") (pin "KK") (pinfunction "31_KK") (pintype "bidirectional"))
      (node (ref "J1") (pin "M") (pinfunction "11_M") (pintype "bidirectional"))
      (node (ref "J1") (pin "MM") (pinfunction "33_MM") (pintype "bidirectional"))
      (node (ref "J1") (pin "N") (pinfunction "12_N") (pintype "bidirectional"))
      (node (ref "J1") (pin "P") (pinfunction "13_P") (pintype "bidirectional"))
      (node (ref "J1") (pin "PP") (pinfunction "35_PP") (pintype "bidirectional"))
      (node (ref "J1") (pin "S") (pinfunction "15_S") (pintype "bidirectional"))
      (node (ref "J1") (pin "U") (pinfunction "17_U") (pintype "bidirectional"))
      (node (ref "J1") (pin "V") (pinfunction "18_V") (pintype "bidirectional"))
      (node (ref "J1") (pin "W") (pinfunction "19_W") (pintype "bidirectional"))
      (node (ref "J1") (pin "Y") (pinfunction "21_Y") (pintype "bidirectional"))
      (node (ref "OMNIBUS") (pin "AC2") (pinfunction "1_AC2") (pintype "bidirectional"))
      (node (ref "OMNIBUS") (pin "AF1") (pinfunction "1_AF1") (pintype "bidirectional"))
      (node (ref "OMNIBUS") (pin "AF2") (pinfunction "1_AF2") (pintype "bidirectional"))
      (node (ref "OMNIBUS") (pin "AN1") (pinfunction "1_AN1") (pintype "bidirectional"))
      (node (ref "OMNIBUS") (pin "AN2") (pinfunction "1_AN2") (pintype "bidirectional"))
      (node (ref "OMNIBUS") (pin "AT1") (pinfunction "1_AT1") (pintype "bidirectional"))
      (node (ref "OMNIBUS") (pin "AT2") (pinfunction "1_AT2") (pintype "bidirectional"))
      (node (ref "OMNIBUS") (pin "BC1") (pinfunction "1_BC1") (pintype "bidirectional"))
      (node (ref "OMNIBUS") (pin "BC2") (pinfunction "1_BC2") (pintype "bidirectional"))
      (node (ref "OMNIBUS") (pin "BF1") (pinfunction "1_BF1") (pintype "bidirectional"))
      (node (ref "OMNIBUS") (pin "BF2") (pinfunction "1_BF2") (pintype "bidirectional"))
      (node (ref "OMNIBUS") (pin "BN1") (pinfunction "1_BN1") (pintype "bidirectional"))
      (node (ref "OMNIBUS") (pin "BN2") (pinfunction "1_BN2") (pintype "bidirectional"))
      (node (ref "OMNIBUS") (pin "BT1") (pinfunction "1_BT1") (pintype "bidirectional"))
      (node (ref "OMNIBUS") (pin "BT2") (pinfunction "1_BT2") (pintype "bidirectional"))
      (node (ref "OMNIBUS") (pin "CC1") (pinfunction "1_CC1") (pintype "bidirectional"))
      (node (ref "OMNIBUS") (pin "CC2") (pinfunction "1_CC2") (pintype "bidirectional"))
      (node (ref "OMNIBUS") (pin "CF1") (pinfunction "1_CF1") (pintype "bidirectional"))
      (node (ref "OMNIBUS") (pin "CF2") (pinfunction "1_CF2") (pintype "bidirectional"))
      (node (ref "OMNIBUS") (pin "CN1") (pinfunction "1_CN1") (pintype "bidirectional"))
      (node (ref "OMNIBUS") (pin "CN2") (pinfunction "1_CN2") (pintype "bidirectional"))
      (node (ref "OMNIBUS") (pin "CT1") (pinfunction "1_CT1") (pintype "bidirectional"))
      (node (ref "OMNIBUS") (pin "CT2") (pinfunction "1_CT2") (pintype "bidirectional"))
      (node (ref "OMNIBUS") (pin "DC1") (pinfunction "1_DC1") (pintype "bidirectional"))
      (node (ref "OMNIBUS") (pin "DC2") (pinfunction "1_DC2") (pintype "bidirectional"))
      (node (ref "OMNIBUS") (pin "DF1") (pinfunction "1_DF1") (pintype "bidirectional"))
      (node (ref "OMNIBUS") (pin "DF2") (pinfunction "1_DF2") (pintype "bidirectional"))
      (node (ref "OMNIBUS") (pin "DN1") (pinfunction "1_DN1") (pintype "bidirectional"))
      (node (ref "OMNIBUS") (pin "DN2") (pinfunction "1_DN2") (pintype "bidirectional"))
      (node (ref "OMNIBUS") (pin "DT1") (pinfunction "1_DT1") (pintype "bidirectional"))
      (node (ref "OMNIBUS") (pin "DT2") (pinfunction "1_DT2") (pintype "bidirectional"))
      (node (ref "Q1") (pin "1") (pinfunction "E_1") (pintype "passive"))
      (node (ref "Q10") (pin "1") (pinfunction "E_1") (pintype "passive"))
      (node (ref "Q19") (pin "1") (pinfunction "E_1") (pintype "passive"))
      (node (ref "Q2") (pin "1") (pinfunction "E_1") (pintype "passive"))
      (node (ref "Q20") (pin "1") (pinfunction "E_1") (pintype "passive"))
      (node (ref "Q21") (pin "1") (pinfunction "E_1") (pintype "passive"))
      (node (ref "Q22") (pin "1") (pinfunction "E_1") (pintype "passive"))
      (node (ref "Q23") (pin "1") (pinfunction "E_1") (pintype "passive"))
      (node (ref "Q24") (pin "1") (pinfunction "E_1") (pintype "passive"))
      (node (ref "Q25") (pin "1") (pinfunction "E_1") (pintype "passive"))
      (node (ref "Q26") (pin "1") (pinfunction "E_1") (pintype "passive"))
      (node (ref "Q27") (pin "1") (pinfunction "E_1") (pintype "passive"))
      (node (ref "Q28") (pin "1") (pinfunction "E_1") (pintype "passive"))
      (node (ref "Q3") (pin "1") (pinfunction "E_1") (pintype "passive"))
      (node (ref "Q4") (pin "1") (pinfunction "E_1") (pintype "passive"))
      (node (ref "Q5") (pin "1") (pinfunction "E_1") (pintype "passive"))
      (node (ref "Q6") (pin "1") (pinfunction "E_1") (pintype "passive"))
      (node (ref "Q7") (pin "1") (pinfunction "E_1") (pintype "passive"))
      (node (ref "Q8") (pin "1") (pinfunction "E_1") (pintype "passive"))
      (node (ref "Q9") (pin "1") (pinfunction "E_1") (pintype "passive"))
      (node (ref "R10") (pin "1") (pinfunction "1_1") (pintype "passive"))
      (node (ref "R102") (pin "1") (pinfunction "1_1") (pintype "passive"))
      (node (ref "R141") (pin "1") (pinfunction "1_1") (pintype "passive"))
      (node (ref "R15") (pin "1") (pinfunction "1_1") (pintype "passive"))
      (node (ref "R49") (pin "1") (pinfunction "1_1") (pintype "passive"))
      (node (ref "R52") (pin "1") (pinfunction "1_1") (pintype "passive"))
      (node (ref "R53") (pin "1") (pinfunction "1_1") (pintype "passive"))
      (node (ref "R54") (pin "1") (pinfunction "1_1") (pintype "passive"))
      (node (ref "R64") (pin "1") (pinfunction "1_1") (pintype "passive"))
      (node (ref "R71") (pin "1") (pinfunction "1_1") (pintype "passive"))
      (node (ref "R87") (pin "2") (pinfunction "2_2") (pintype "passive"))
      (node (ref "R97") (pin "1") (pinfunction "1_1") (pintype "passive"))
    )
    (net (code "71") (name "Net-(C26-Pad+)") (class "Default")
      (node (ref "C26") (pin "+") (pinfunction "+_+") (pintype "passive"))
      (node (ref "R50") (pin "E") (pinfunction "E_E") (pintype "passive"))
      (node (ref "R52") (pin "2") (pinfunction "2_2") (pintype "passive"))
      (node (ref "R55") (pin "E") (pinfunction "E_E") (pintype "passive"))
    )
    (net (code "72") (name "Net-(C28-Pad1)") (class "Default")
      (node (ref "C28") (pin "1") (pinfunction "1_1") (pintype "passive"))
      (node (ref "R69") (pin "2") (pinfunction "2_2") (pintype "passive"))
    )
    (net (code "73") (name "Net-(C33-Pad1)") (class "Default")
      (node (ref "C33") (pin "1") (pinfunction "1_1") (pintype "passive"))
      (node (ref "R81") (pin "1") (pinfunction "1_1") (pintype "passive"))
      (node (ref "R82") (pin "2") (pinfunction "2_2") (pintype "passive"))
    )
    (net (code "74") (name "Net-(C34-Pad1)") (class "Default")
      (node (ref "C34") (pin "1") (pinfunction "1_1") (pintype "passive"))
      (node (ref "R70") (pin "2") (pinfunction "2_2") (pintype "passive"))
      (node (ref "R72") (pin "1") (pinfunction "1_1") (pintype "passive"))
      (node (ref "R73") (pin "1") (pinfunction "1_1") (pintype "passive"))
      (node (ref "R74") (pin "2") (pinfunction "2_2") (pintype "passive"))
      (node (ref "R84") (pin "2") (pinfunction "2_2") (pintype "passive"))
      (node (ref "W5") (pin "2") (pinfunction "2_2") (pintype "passive"))
    )
    (net (code "75") (name "Net-(C35-Pad1)") (class "Default")
      (node (ref "C35") (pin "1") (pinfunction "1_1") (pintype "passive"))
      (node (ref "R93") (pin "1") (pinfunction "1_1") (pintype "passive"))
      (node (ref "R94") (pin "2") (pinfunction "2_2") (pintype "passive"))
    )
    (net (code "76") (name "Net-(C36-Pad1)") (class "Default")
      (node (ref "C36") (pin "1") (pinfunction "1_1") (pintype "passive"))
      (node (ref "R139") (pin "2") (pinfunction "2_2") (pintype "passive"))
    )
    (net (code "77") (name "Net-(C41-Pad1)") (class "Default")
      (node (ref "C41") (pin "1") (pinfunction "1_1") (pintype "passive"))
      (node (ref "R140") (pin "2") (pinfunction "2_2") (pintype "passive"))
      (node (ref "R142") (pin "1") (pinfunction "1_1") (pintype "passive"))
      (node (ref "R143") (pin "1") (pinfunction "1_1") (pintype "passive"))
      (node (ref "R144") (pin "2") (pinfunction "2_2") (pintype "passive"))
      (node (ref "R149") (pin "2") (pinfunction "2_2") (pintype "passive"))
      (node (ref "W6") (pin "2") (pinfunction "2_2") (pintype "passive"))
    )
    (net (code "78") (name "Net-(D1-PadA)") (class "Default")
      (node (ref "D1") (pin "A") (pinfunction "A_A") (pintype "passive"))
      (node (ref "D2") (pin "A") (pinfunction "A_A") (pintype "passive"))
      (node (ref "R12") (pin "1") (pinfunction "1_1") (pintype "passive"))
    )
    (net (code "79") (name "Net-(D3-PadA)") (class "Default")
      (node (ref "D3") (pin "A") (pinfunction "A_A") (pintype "passive"))
      (node (ref "R11") (pin "1") (pinfunction "1_1") (pintype "passive"))
      (node (ref "R12") (pin "2") (pinfunction "2_2") (pintype "passive"))
    )
    (net (code "80") (name "Net-(D4-PadA)") (class "Default")
      (node (ref "D4") (pin "A") (pinfunction "A_A") (pintype "passive"))
      (node (ref "D5") (pin "A") (pinfunction "A_A") (pintype "passive"))
      (node (ref "R17") (pin "1") (pinfunction "1_1") (pintype "passive"))
    )
    (net (code "81") (name "Net-(D6-PadA)") (class "Default")
      (node (ref "D6") (pin "A") (pinfunction "A_A") (pintype "passive"))
      (node (ref "R16") (pin "1") (pinfunction "1_1") (pintype "passive"))
      (node (ref "R17") (pin "2") (pinfunction "2_2") (pintype "passive"))
    )
    (net (code "82") (name "Net-(D7-PadA)") (class "Default")
      (node (ref "D7") (pin "A") (pinfunction "A_A") (pintype "passive"))
      (node (ref "R19") (pin "1") (pinfunction "1_1") (pintype "passive"))
      (node (ref "R20") (pin "2") (pinfunction "2_2") (pintype "passive"))
    )
    (net (code "83") (name "Net-(D9-PadA)") (class "Default")
      (node (ref "D9") (pin "A") (pinfunction "A_A") (pintype "passive"))
      (node (ref "R22") (pin "1") (pinfunction "1_1") (pintype "passive"))
      (node (ref "R23") (pin "2") (pinfunction "2_2") (pintype "passive"))
    )
    (net (code "84") (name "Net-(D11-PadA)") (class "Default")
      (node (ref "D11") (pin "A") (pinfunction "A_A") (pintype "passive"))
      (node (ref "R25") (pin "1") (pinfunction "1_1") (pintype "passive"))
      (node (ref "R26") (pin "2") (pinfunction "2_2") (pintype "passive"))
    )
    (net (code "85") (name "Net-(D13-PadA)") (class "Default")
      (node (ref "D13") (pin "A") (pinfunction "A_A") (pintype "passive"))
      (node (ref "R28") (pin "1") (pinfunction "1_1") (pintype "passive"))
      (node (ref "R29") (pin "E") (pinfunction "E_E") (pintype "passive"))
      (node (ref "W3") (pin "1") (pinfunction "1_1") (pintype "passive"))
    )
    (net (code "86") (name "Net-(D15-PadA)") (class "Default")
      (node (ref "D15") (pin "A") (pinfunction "A_A") (pintype "passive"))
      (node (ref "R33") (pin "1") (pinfunction "1_1") (pintype "passive"))
      (node (ref "R34") (pin "E") (pinfunction "E_E") (pintype "passive"))
    )
    (net (code "87") (name "Net-(D17-PadA)") (class "Default")
      (node (ref "D17") (pin "A") (pinfunction "A_A") (pintype "passive"))
      (node (ref "R37") (pin "1") (pinfunction "1_1") (pintype "passive"))
      (node (ref "R38") (pin "E") (pinfunction "E_E") (pintype "passive"))
    )
    (net (code "88") (name "Net-(D19-PadA)") (class "Default")
      (node (ref "D19") (pin "A") (pinfunction "A_A") (pintype "passive"))
      (node (ref "R41") (pin "1") (pinfunction "1_1") (pintype "passive"))
      (node (ref "R42") (pin "E") (pinfunction "E_E") (pintype "passive"))
    )
    (net (code "89") (name "Net-(D21-PadA)") (class "Default")
      (node (ref "D21") (pin "A") (pinfunction "A_A") (pintype "passive"))
      (node (ref "R45") (pin "1") (pinfunction "1_1") (pintype "passive"))
      (node (ref "R46") (pin "E") (pinfunction "E_E") (pintype "passive"))
    )
    (net (code "90") (name "Net-(D30-PadA)") (class "Default")
      (node (ref "D30") (pin "A") (pinfunction "A_A") (pintype "passive"))
      (node (ref "D31") (pin "A") (pinfunction "A_A") (pintype "passive"))
      (node (ref "R99") (pin "1") (pinfunction "1_1") (pintype "passive"))
    )
    (net (code "91") (name "Net-(D32-PadA)") (class "Default")
      (node (ref "D32") (pin "A") (pinfunction "A_A") (pintype "passive"))
      (node (ref "R98") (pin "1") (pinfunction "1_1") (pintype "passive"))
      (node (ref "R99") (pin "2") (pinfunction "2_2") (pintype "passive"))
    )
    (net (code "92") (name "Net-(D33-PadA)") (class "Default")
      (node (ref "D33") (pin "A") (pinfunction "A_A") (pintype "passive"))
      (node (ref "D34") (pin "A") (pinfunction "A_A") (pintype "passive"))
      (node (ref "R104") (pin "1") (pinfunction "1_1") (pintype "passive"))
    )
    (net (code "93") (name "Net-(D35-PadA)") (class "Default")
      (node (ref "D35") (pin "A") (pinfunction "A_A") (pintype "passive"))
      (node (ref "R103") (pin "1") (pinfunction "1_1") (pintype "passive"))
      (node (ref "R104") (pin "2") (pinfunction "2_2") (pintype "passive"))
    )
    (net (code "94") (name "Net-(D36-PadA)") (class "Default")
      (node (ref "D36") (pin "A") (pinfunction "A_A") (pintype "passive"))
      (node (ref "R106") (pin "1") (pinfunction "1_1") (pintype "passive"))
      (node (ref "R107") (pin "2") (pinfunction "2_2") (pintype "passive"))
    )
    (net (code "95") (name "Net-(D38-PadA)") (class "Default")
      (node (ref "D38") (pin "A") (pinfunction "A_A") (pintype "passive"))
      (node (ref "R109") (pin "1") (pinfunction "1_1") (pintype "passive"))
      (node (ref "R110") (pin "2") (pinfunction "2_2") (pintype "passive"))
    )
    (net (code "96") (name "Net-(D40-PadA)") (class "Default")
      (node (ref "D40") (pin "A") (pinfunction "A_A") (pintype "passive"))
      (node (ref "R112") (pin "1") (pinfunction "1_1") (pintype "passive"))
      (node (ref "R113") (pin "2") (pinfunction "2_2") (pintype "passive"))
    )
    (net (code "97") (name "Net-(D42-PadA)") (class "Default")
      (node (ref "D42") (pin "A") (pinfunction "A_A") (pintype "passive"))
      (node (ref "R115") (pin "1") (pinfunction "1_1") (pintype "passive"))
      (node (ref "R116") (pin "E") (pinfunction "E_E") (pintype "passive"))
      (node (ref "W2") (pin "1") (pinfunction "1_1") (pintype "passive"))
    )
    (net (code "98") (name "Net-(D44-PadA)") (class "Default")
      (node (ref "D44") (pin "A") (pinfunction "A_A") (pintype "passive"))
      (node (ref "R120") (pin "1") (pinfunction "1_1") (pintype "passive"))
      (node (ref "R121") (pin "E") (pinfunction "E_E") (pintype "passive"))
    )
    (net (code "99") (name "Net-(D46-PadA)") (class "Default")
      (node (ref "D46") (pin "A") (pinfunction "A_A") (pintype "passive"))
      (node (ref "R124") (pin "1") (pinfunction "1_1") (pintype "passive"))
      (node (ref "R125") (pin "E") (pinfunction "E_E") (pintype "passive"))
    )
    (net (code "100") (name "Net-(D48-PadA)") (class "Default")
      (node (ref "D48") (pin "A") (pinfunction "A_A") (pintype "passive"))
      (node (ref "R128") (pin "1") (pinfunction "1_1") (pintype "passive"))
      (node (ref "R129") (pin "E") (pinfunction "E_E") (pintype "passive"))
    )
    (net (code "101") (name "Net-(D50-PadA)") (class "Default")
      (node (ref "D50") (pin "A") (pinfunction "A_A") (pintype "passive"))
      (node (ref "R132") (pin "1") (pinfunction "1_1") (pintype "passive"))
      (node (ref "R133") (pin "E") (pinfunction "E_E") (pintype "passive"))
    )
    (net (code "102") (name "Net-(D54-PadA)") (class "Default")
      (node (ref "D54") (pin "A") (pinfunction "A_A") (pintype "passive"))
      (node (ref "D55") (pin "A") (pinfunction "A_A") (pintype "passive"))
    )
    (net (code "103") (name "Net-(D56-PadA)") (class "Default")
      (node (ref "D56") (pin "A") (pinfunction "A_A") (pintype "passive"))
      (node (ref "D57") (pin "A") (pinfunction "A_A") (pintype "passive"))
    )
    (net (code "104") (name "Net-(E1A-DN)") (class "Default")
      (node (ref "E1") (pin "4") (pinfunction "DN_4") (pintype "input"))
      (node (ref "E4") (pin "13") (pinfunction "BO_13") (pintype "output"))
    )
    (net (code "105") (name "Net-(E1A-UP)") (class "Default")
      (node (ref "E1") (pin "5") (pinfunction "UP_5") (pintype "input"))
      (node (ref "E4") (pin "12") (pinfunction "CO_12") (pintype "output"))
    )
    (net (code "106") (name "Net-(E2A-DN)") (class "Default")
      (node (ref "E2") (pin "4") (pinfunction "DN_4") (pintype "input"))
      (node (ref "E5") (pin "13") (pinfunction "BO_13") (pintype "output"))
    )
    (net (code "107") (name "Net-(E2A-UP)") (class "Default")
      (node (ref "E2") (pin "5") (pinfunction "UP_5") (pintype "input"))
      (node (ref "E5") (pin "12") (pinfunction "CO_12") (pintype "output"))
    )
    (net (code "108") (name "Net-(E4A-DN)") (class "Default")
      (node (ref "E4") (pin "4") (pinfunction "DN_4") (pintype "input"))
      (node (ref "E7") (pin "13") (pinfunction "BO_13") (pintype "output"))
    )
    (net (code "109") (name "Net-(E4A-UP)") (class "Default")
      (node (ref "E4") (pin "5") (pinfunction "UP_5") (pintype "input"))
      (node (ref "E7") (pin "12") (pinfunction "CO_12") (pintype "output"))
    )
    (net (code "110") (name "Net-(E5A-DN)") (class "Default")
      (node (ref "E5") (pin "4") (pinfunction "DN_4") (pintype "input"))
      (node (ref "E8") (pin "13") (pinfunction "BO_13") (pintype "output"))
    )
    (net (code "111") (name "Net-(E5A-UP)") (class "Default")
      (node (ref "E5") (pin "5") (pinfunction "UP_5") (pintype "input"))
      (node (ref "E8") (pin "12") (pinfunction "CO_12") (pintype "output"))
    )
    (net (code "112") (name "Net-(E10A-O)") (class "Default")
      (node (ref "E10") (pin "2") (pinfunction "O_2") (pintype "output"))
      (node (ref "E9") (pin "14") (pinfunction "B3_14") (pintype "input"))
    )
    (net (code "113") (name "Net-(E10B-O)") (class "Default")
      (node (ref "E10") (pin "4") (pinfunction "O_4") (pintype "output"))
      (node (ref "E11") (pin "5") (pinfunction "B1_5") (pintype "input"))
    )
    (net (code "114") (name "Net-(E10C-O)") (class "Default")
      (node (ref "E10") (pin "6") (pinfunction "O_6") (pintype "output"))
      (node (ref "E11") (pin "2") (pinfunction "B0_2") (pintype "input"))
    )
    (net (code "115") (name "Net-(E10D-O)") (class "Default")
      (node (ref "E10") (pin "8") (pinfunction "O_8") (pintype "output"))
      (node (ref "E11") (pin "14") (pinfunction "B3_14") (pintype "input"))
    )
    (net (code "116") (name "Net-(E10E-O)") (class "Default")
      (node (ref "E10") (pin "10") (pinfunction "O_10") (pintype "output"))
      (node (ref "E11") (pin "11") (pinfunction "B2_11") (pintype "input"))
    )
    (net (code "117") (name "Net-(E10F-O)") (class "Default")
      (node (ref "E10") (pin "12") (pinfunction "O_12") (pintype "output"))
      (node (ref "E9") (pin "11") (pinfunction "B2_11") (pintype "input"))
    )
    (net (code "118") (name "Net-(E12A-O)") (class "Default")
      (node (ref "E12") (pin "2") (pinfunction "O_2") (pintype "output"))
      (node (ref "R44") (pin "1") (pinfunction "1_1") (pintype "passive"))
    )
    (net (code "119") (name "Net-(E12B-O)") (class "Default")
      (node (ref "E12") (pin "4") (pinfunction "O_4") (pintype "output"))
      (node (ref "E13") (pin "5") (pinfunction "B1_5") (pintype "input"))
    )
    (net (code "120") (name "Net-(E12C-O)") (class "Default")
      (node (ref "E12") (pin "6") (pinfunction "O_6") (pintype "output"))
      (node (ref "E13") (pin "2") (pinfunction "B0_2") (pintype "input"))
    )
    (net (code "121") (name "Net-(E12D-O)") (class "Default")
      (node (ref "E12") (pin "8") (pinfunction "O_8") (pintype "output"))
      (node (ref "E9") (pin "5") (pinfunction "B1_5") (pintype "input"))
    )
    (net (code "122") (name "Net-(E12E-O)") (class "Default")
      (node (ref "E12") (pin "10") (pinfunction "O_10") (pintype "output"))
      (node (ref "E9") (pin "2") (pinfunction "B0_2") (pintype "input"))
    )
    (net (code "123") (name "Net-(E12F-O)") (class "Default")
      (node (ref "E12") (pin "12") (pinfunction "O_12") (pintype "output"))
      (node (ref "R131") (pin "1") (pinfunction "1_1") (pintype "passive"))
    )
    (net (code "124") (name "Net-(E14-+IN)") (class "Default")
      (node (ref "E14") (pin "3") (pinfunction "+IN_3") (pintype "input"))
      (node (ref "R50") (pin "S") (pinfunction "S_S") (pintype "passive"))
    )
    (net (code "125") (name "Net-(E15-+IN)") (class "Default")
      (node (ref "E15") (pin "3") (pinfunction "+IN_3") (pintype "input"))
      (node (ref "R55") (pin "S") (pinfunction "S_S") (pintype "passive"))
    )
    (net (code "126") (name "Net-(E16-+IN)") (class "Default")
      (node (ref "E16") (pin "3") (pinfunction "+IN_3") (pintype "input"))
      (node (ref "R71") (pin "2") (pinfunction "2_2") (pintype "passive"))
    )
    (net (code "127") (name "Net-(E16--IN)") (class "Default")
      (node (ref "C34") (pin "2") (pinfunction "2_2") (pintype "passive"))
      (node (ref "D10") (pin "C") (pinfunction "C_C") (pintype "passive"))
      (node (ref "D12") (pin "C") (pinfunction "C_C") (pintype "passive"))
      (node (ref "D14") (pin "C") (pinfunction "C_C") (pintype "passive"))
      (node (ref "D16") (pin "C") (pinfunction "C_C") (pintype "passive"))
      (node (ref "D18") (pin "C") (pinfunction "C_C") (pintype "passive"))
      (node (ref "D2") (pin "C") (pinfunction "C_C") (pintype "passive"))
      (node (ref "D20") (pin "C") (pinfunction "C_C") (pintype "passive"))
      (node (ref "D22") (pin "C") (pinfunction "C_C") (pintype "passive"))
      (node (ref "D5") (pin "C") (pinfunction "C_C") (pintype "passive"))
      (node (ref "D8") (pin "C") (pinfunction "C_C") (pintype "passive"))
      (node (ref "E16") (pin "2") (pinfunction "-IN_2") (pintype "input"))
      (node (ref "R82") (pin "1") (pinfunction "1_1") (pintype "passive"))
      (node (ref "R83") (pin "1") (pinfunction "1_1") (pintype "passive"))
      (node (ref "R85") (pin "2") (pinfunction "2_2") (pintype "passive"))
    )
    (net (code "128") (name "Net-(E16-ON1)") (class "Default")
      (node (ref "E16") (pin "1") (pinfunction "ON1_1") (pintype "passive"))
      (node (ref "R69") (pin "1") (pinfunction "1_1") (pintype "passive"))
    )
    (net (code "129") (name "Net-(E16-ON2)") (class "Default")
      (node (ref "C28") (pin "2") (pinfunction "2_2") (pintype "passive"))
      (node (ref "E16") (pin "8") (pinfunction "ON2_8") (pintype "passive"))
    )
    (net (code "130") (name "Net-(E16-OPT)") (class "Default")
      (node (ref "E16") (pin "5") (pinfunction "OPT_5") (pintype "passive"))
      (node (ref "R72") (pin "2") (pinfunction "2_2") (pintype "passive"))
    )
    (net (code "131") (name "Net-(E16-OUT)") (class "Default")
      (node (ref "D25") (pin "C") (pinfunction "C_C") (pintype "passive"))
      (node (ref "D26") (pin "C") (pinfunction "C_C") (pintype "passive"))
      (node (ref "D56") (pin "C") (pinfunction "C_C") (pintype "passive"))
      (node (ref "E16") (pin "6") (pinfunction "OUT_6") (pintype "output"))
    )
    (net (code "132") (name "Net-(E16-V+)") (class "Default")
      (node (ref "C30") (pin "+") (pinfunction "+_+") (pintype "passive"))
      (node (ref "E16") (pin "7") (pinfunction "V+_7") (pintype "power_in"))
      (node (ref "R66") (pin "1") (pinfunction "1_1") (pintype "passive"))
      (node (ref "R67") (pin "1") (pinfunction "1_1") (pintype "passive"))
      (node (ref "R68") (pin "1") (pinfunction "1_1") (pintype "passive"))
    )
    (net (code "133") (name "Net-(E16-V-)") (class "Default")
      (node (ref "C32") (pin "-") (pinfunction "-_-") (pintype "passive"))
      (node (ref "E16") (pin "4") (pinfunction "V-_4") (pintype "power_in"))
      (node (ref "R75") (pin "1") (pinfunction "1_1") (pintype "passive"))
      (node (ref "R76") (pin "1") (pinfunction "1_1") (pintype "passive"))
      (node (ref "R80") (pin "2") (pinfunction "2_2") (pintype "passive"))
    )
    (net (code "134") (name "Net-(E17-+IN)") (class "Default")
      (node (ref "E17") (pin "3") (pinfunction "+IN_3") (pintype "input"))
      (node (ref "R141") (pin "2") (pinfunction "2_2") (pintype "passive"))
    )
    (net (code "135") (name "Net-(E17--IN)") (class "Default")
      (node (ref "C41") (pin "2") (pinfunction "2_2") (pintype "passive"))
      (node (ref "D31") (pin "C") (pinfunction "C_C") (pintype "passive"))
      (node (ref "D34") (pin "C") (pinfunction "C_C") (pintype "passive"))
      (node (ref "D37") (pin "C") (pinfunction "C_C") (pintype "passive"))
      (node (ref "D39") (pin "C") (pinfunction "C_C") (pintype "passive"))
      (node (ref "D41") (pin "C") (pinfunction "C_C") (pintype "passive"))
      (node (ref "D43") (pin "C") (pinfunction "C_C") (pintype "passive"))
      (node (ref "D45") (pin "C") (pinfunction "C_C") (pintype "passive"))
      (node (ref "D47") (pin "C") (pinfunction "C_C") (pintype "passive"))
      (node (ref "D49") (pin "C") (pinfunction "C_C") (pintype "passive"))
      (node (ref "D51") (pin "C") (pinfunction "C_C") (pintype "passive"))
      (node (ref "E17") (pin "2") (pinfunction "-IN_2") (pintype "input"))
      (node (ref "R148") (pin "1") (pinfunction "1_1") (pintype "passive"))
      (node (ref "R92") (pin "2") (pinfunction "2_2") (pintype "passive"))
      (node (ref "R94") (pin "1") (pinfunction "1_1") (pintype "passive"))
    )
    (net (code "136") (name "Net-(E17-ON1)") (class "Default")
      (node (ref "E17") (pin "1") (pinfunction "ON1_1") (pintype "passive"))
      (node (ref "R139") (pin "1") (pinfunction "1_1") (pintype "passive"))
    )
    (net (code "137") (name "Net-(E17-ON2)") (class "Default")
      (node (ref "C36") (pin "2") (pinfunction "2_2") (pintype "passive"))
      (node (ref "E17") (pin "8") (pinfunction "ON2_8") (pintype "passive"))
    )
    (net (code "138") (name "Net-(E17-OPT)") (class "Default")
      (node (ref "E17") (pin "5") (pinfunction "OPT_5") (pintype "passive"))
      (node (ref "R142") (pin "2") (pinfunction "2_2") (pintype "passive"))
    )
    (net (code "139") (name "Net-(E17-OUT)") (class "Default")
      (node (ref "D52") (pin "C") (pinfunction "C_C") (pintype "passive"))
      (node (ref "D53") (pin "C") (pinfunction "C_C") (pintype "passive"))
      (node (ref "D54") (pin "C") (pinfunction "C_C") (pintype "passive"))
      (node (ref "E17") (pin "6") (pinfunction "OUT_6") (pintype "output"))
    )
    (net (code "140") (name "Net-(E17-V+)") (class "Default")
      (node (ref "C38") (pin "+") (pinfunction "+_+") (pintype "passive"))
      (node (ref "E17") (pin "7") (pinfunction "V+_7") (pintype "power_in"))
      (node (ref "R136") (pin "2") (pinfunction "2_2") (pintype "passive"))
      (node (ref "R137") (pin "2") (pinfunction "2_2") (pintype "passive"))
      (node (ref "R138") (pin "1") (pinfunction "1_1") (pintype "passive"))
    )
    (net (code "141") (name "Net-(E17-V-)") (class "Default")
      (node (ref "C40") (pin "-") (pinfunction "-_-") (pintype "passive"))
      (node (ref "E17") (pin "4") (pinfunction "V-_4") (pintype "power_in"))
      (node (ref "R145") (pin "1") (pinfunction "1_1") (pintype "passive"))
      (node (ref "R146") (pin "1") (pinfunction "1_1") (pintype "passive"))
      (node (ref "R147") (pin "2") (pinfunction "2_2") (pintype "passive"))
    )
    (net (code "142") (name "Net-(OMNIBUSDH-1)") (class "Default")
      (node (ref "OMNIBUS") (pin "DB2") (pinfunction "1_DB2") (pintype "bidirectional"))
      (node (ref "R62") (pin "1") (pinfunction "1_1") (pintype "passive"))
      (node (ref "R63") (pin "1") (pinfunction "1_1") (pintype "passive"))
    )
    (net (code "143") (name "Net-(Q1-B)") (class "Default")
      (node (ref "Q1") (pin "2") (pinfunction "B_2") (pintype "passive"))
      (node (ref "R8") (pin "2") (pinfunction "2_2") (pintype "passive"))
    )
    (net (code "144") (name "Net-(Q1-C)") (class "Default")
      (node (ref "D1") (pin "C") (pinfunction "C_C") (pintype "passive"))
      (node (ref "Q1") (pin "3") (pinfunction "C_3") (pintype "passive"))
      (node (ref "R10") (pin "2") (pinfunction "2_2") (pintype "passive"))
      (node (ref "R9") (pin "1") (pinfunction "1_1") (pintype "passive"))
    )
    (net (code "145") (name "Net-(Q2-B)") (class "Default")
      (node (ref "Q2") (pin "2") (pinfunction "B_2") (pintype "passive"))
      (node (ref "R13") (pin "2") (pinfunction "2_2") (pintype "passive"))
    )
    (net (code "146") (name "Net-(Q2-C)") (class "Default")
      (node (ref "D4") (pin "C") (pinfunction "C_C") (pintype "passive"))
      (node (ref "Q2") (pin "3") (pinfunction "C_3") (pintype "passive"))
      (node (ref "R14") (pin "1") (pinfunction "1_1") (pintype "passive"))
      (node (ref "R15") (pin "2") (pinfunction "2_2") (pintype "passive"))
    )
    (net (code "147") (name "Net-(Q3-B)") (class "Default")
      (node (ref "Q3") (pin "2") (pinfunction "B_2") (pintype "passive"))
      (node (ref "R18") (pin "2") (pinfunction "2_2") (pintype "passive"))
    )
    (net (code "148") (name "Net-(Q3-C)") (class "Default")
      (node (ref "D8") (pin "A") (pinfunction "A_A") (pintype "passive"))
      (node (ref "Q3") (pin "3") (pinfunction "C_3") (pintype "passive"))
      (node (ref "R20") (pin "1") (pinfunction "1_1") (pintype "passive"))
    )
    (net (code "149") (name "Net-(Q4-B)") (class "Default")
      (node (ref "Q4") (pin "2") (pinfunction "B_2") (pintype "passive"))
      (node (ref "R21") (pin "2") (pinfunction "2_2") (pintype "passive"))
    )
    (net (code "150") (name "Net-(Q4-C)") (class "Default")
      (node (ref "D10") (pin "A") (pinfunction "A_A") (pintype "passive"))
      (node (ref "Q4") (pin "3") (pinfunction "C_3") (pintype "passive"))
      (node (ref "R23") (pin "1") (pinfunction "1_1") (pintype "passive"))
    )
    (net (code "151") (name "Net-(Q5-B)") (class "Default")
      (node (ref "Q5") (pin "2") (pinfunction "B_2") (pintype "passive"))
      (node (ref "R24") (pin "2") (pinfunction "2_2") (pintype "passive"))
    )
    (net (code "152") (name "Net-(Q5-C)") (class "Default")
      (node (ref "D12") (pin "A") (pinfunction "A_A") (pintype "passive"))
      (node (ref "Q5") (pin "3") (pinfunction "C_3") (pintype "passive"))
      (node (ref "R26") (pin "1") (pinfunction "1_1") (pintype "passive"))
    )
    (net (code "153") (name "Net-(Q6-B)") (class "Default")
      (node (ref "Q6") (pin "2") (pinfunction "B_2") (pintype "passive"))
      (node (ref "R27") (pin "2") (pinfunction "2_2") (pintype "passive"))
    )
    (net (code "154") (name "Net-(Q6-C)") (class "Default")
      (node (ref "D14") (pin "A") (pinfunction "A_A") (pintype "passive"))
      (node (ref "Q6") (pin "3") (pinfunction "C_3") (pintype "passive"))
      (node (ref "R31") (pin "1") (pinfunction "1_1") (pintype "passive"))
    )
    (net (code "155") (name "Net-(Q7-B)") (class "Default")
      (node (ref "Q7") (pin "2") (pinfunction "B_2") (pintype "passive"))
      (node (ref "R32") (pin "2") (pinfunction "2_2") (pintype "passive"))
    )
    (net (code "156") (name "Net-(Q7-C)") (class "Default")
      (node (ref "D16") (pin "A") (pinfunction "A_A") (pintype "passive"))
      (node (ref "Q7") (pin "3") (pinfunction "C_3") (pintype "passive"))
      (node (ref "R35") (pin "1") (pinfunction "1_1") (pintype "passive"))
    )
    (net (code "157") (name "Net-(Q8-B)") (class "Default")
      (node (ref "Q8") (pin "2") (pinfunction "B_2") (pintype "passive"))
      (node (ref "R36") (pin "2") (pinfunction "2_2") (pintype "passive"))
    )
    (net (code "158") (name "Net-(Q8-C)") (class "Default")
      (node (ref "D18") (pin "A") (pinfunction "A_A") (pintype "passive"))
      (node (ref "Q8") (pin "3") (pinfunction "C_3") (pintype "passive"))
      (node (ref "R39") (pin "1") (pinfunction "1_1") (pintype "passive"))
    )
    (net (code "159") (name "Net-(Q9-B)") (class "Default")
      (node (ref "Q9") (pin "2") (pinfunction "B_2") (pintype "passive"))
      (node (ref "R40") (pin "2") (pinfunction "2_2") (pintype "passive"))
    )
    (net (code "160") (name "Net-(Q9-C)") (class "Default")
      (node (ref "D20") (pin "A") (pinfunction "A_A") (pintype "passive"))
      (node (ref "Q9") (pin "3") (pinfunction "C_3") (pintype "passive"))
      (node (ref "R43") (pin "1") (pinfunction "1_1") (pintype "passive"))
    )
    (net (code "161") (name "Net-(Q10-B)") (class "Default")
      (node (ref "Q10") (pin "2") (pinfunction "B_2") (pintype "passive"))
      (node (ref "R44") (pin "2") (pinfunction "2_2") (pintype "passive"))
    )
    (net (code "162") (name "Net-(Q10-C)") (class "Default")
      (node (ref "D22") (pin "A") (pinfunction "A_A") (pintype "passive"))
      (node (ref "Q10") (pin "3") (pinfunction "C_3") (pintype "passive"))
      (node (ref "R47") (pin "1") (pinfunction "1_1") (pintype "passive"))
      (node (ref "R48") (pin "1") (pinfunction "1_1") (pintype "passive"))
    )
    (net (code "163") (name "Net-(Q11-B)") (class "Default")
      (node (ref "D24") (pin "A") (pinfunction "A_A") (pintype "passive"))
      (node (ref "Q11") (pin "2") (pinfunction "B_2") (pintype "passive"))
      (node (ref "R53") (pin "2") (pinfunction "2_2") (pintype "passive"))
    )
    (net (code "164") (name "Net-(Q11-C)") (class "Default")
      (node (ref "D23") (pin "C") (pinfunction "C_C") (pintype "passive"))
      (node (ref "Q11") (pin "3") (pinfunction "C_3") (pintype "passive"))
      (node (ref "R50") (pin "A") (pinfunction "A_A") (pintype "passive"))
      (node (ref "R55") (pin "A") (pinfunction "A_A") (pintype "passive"))
    )
    (net (code "165") (name "Net-(Q11-E)") (class "Default")
      (node (ref "Q11") (pin "1") (pinfunction "E_1") (pintype "passive"))
      (node (ref "R51") (pin "1") (pinfunction "1_1") (pintype "passive"))
    )
    (net (code "166") (name "Net-(Q12-B)") (class "Default")
      (node (ref "Q12") (pin "2") (pinfunction "B_2") (pintype "passive"))
      (node (ref "R57") (pin "2") (pinfunction "2_2") (pintype "passive"))
    )
    (net (code "167") (name "Net-(Q12-C)") (class "Default")
      (node (ref "C22") (pin "2") (pinfunction "2_2") (pintype "passive"))
      (node (ref "Q12") (pin "3") (pinfunction "C_3") (pintype "passive"))
      (node (ref "Q14") (pin "2") (pinfunction "B_2") (pintype "passive"))
      (node (ref "R62") (pin "2") (pinfunction "2_2") (pintype "passive"))
    )
    (net (code "168") (name "Net-(Q13-B)") (class "Default")
      (node (ref "Q13") (pin "2") (pinfunction "B_2") (pintype "passive"))
      (node (ref "R61") (pin "2") (pinfunction "2_2") (pintype "passive"))
    )
    (net (code "169") (name "Net-(Q13-C)") (class "Default")
      (node (ref "C23") (pin "1") (pinfunction "1_1") (pintype "passive"))
      (node (ref "Q13") (pin "3") (pinfunction "C_3") (pintype "passive"))
      (node (ref "R60") (pin "1") (pinfunction "1_1") (pintype "passive"))
    )
    (net (code "170") (name "Net-(Q13-E)") (class "Default")
      (node (ref "Q13") (pin "1") (pinfunction "E_1") (pintype "passive"))
      (node (ref "Q14") (pin "1") (pinfunction "E_1") (pintype "passive"))
      (node (ref "R64") (pin "2") (pinfunction "2_2") (pintype "passive"))
      (node (ref "R65") (pin "1") (pinfunction "1_1") (pintype "passive"))
    )
    (net (code "171") (name "Net-(Q14-C)") (class "Default")
      (node (ref "C24") (pin "1") (pinfunction "1_1") (pintype "passive"))
      (node (ref "Q14") (pin "3") (pinfunction "C_3") (pintype "passive"))
      (node (ref "R63") (pin "2") (pinfunction "2_2") (pintype "passive"))
    )
    (net (code "172") (name "Net-(Q15-B)") (class "Default")
      (node (ref "D25") (pin "A") (pinfunction "A_A") (pintype "passive"))
      (node (ref "Q15") (pin "2") (pinfunction "B_2") (pintype "passive"))
      (node (ref "R66") (pin "2") (pinfunction "2_2") (pintype "passive"))
    )
    (net (code "173") (name "Net-(Q15-C)") (class "Default")
      (node (ref "C29") (pin "1") (pinfunction "1_1") (pintype "passive"))
      (node (ref "Q15") (pin "3") (pinfunction "C_3") (pintype "passive"))
      (node (ref "R67") (pin "2") (pinfunction "2_2") (pintype "passive"))
    )
    (net (code "174") (name "Net-(Q15-E)") (class "Default")
      (node (ref "Q15") (pin "1") (pinfunction "E_1") (pintype "passive"))
      (node (ref "R70") (pin "1") (pinfunction "1_1") (pintype "passive"))
    )
    (net (code "175") (name "Net-(Q16-B)") (class "Default")
      (node (ref "D26") (pin "A") (pinfunction "A_A") (pintype "passive"))
      (node (ref "Q16") (pin "2") (pinfunction "B_2") (pintype "passive"))
      (node (ref "R75") (pin "2") (pinfunction "2_2") (pintype "passive"))
    )
    (net (code "176") (name "Net-(Q16-C)") (class "Default")
      (node (ref "C31") (pin "2") (pinfunction "2_2") (pintype "passive"))
      (node (ref "Q16") (pin "3") (pinfunction "C_3") (pintype "passive"))
      (node (ref "R76") (pin "2") (pinfunction "2_2") (pintype "passive"))
    )
    (net (code "177") (name "Net-(Q16-E)") (class "Default")
      (node (ref "Q16") (pin "1") (pinfunction "E_1") (pintype "passive"))
      (node (ref "R74") (pin "1") (pinfunction "1_1") (pintype "passive"))
    )
    (net (code "178") (name "Net-(Q17-B)") (class "Default")
      (node (ref "D29") (pin "C") (pinfunction "C_C") (pintype "passive"))
      (node (ref "Q17") (pin "2") (pinfunction "B_2") (pintype "passive"))
      (node (ref "Q18") (pin "2") (pinfunction "B_2") (pintype "passive"))
      (node (ref "R87") (pin "1") (pinfunction "1_1") (pintype "passive"))
    )
    (net (code "179") (name "Net-(Q17-C)") (class "Default")
      (node (ref "D27") (pin "A") (pinfunction "A_A") (pintype "passive"))
      (node (ref "Q17") (pin "3") (pinfunction "C_3") (pintype "passive"))
      (node (ref "R88") (pin "A") (pinfunction "A_A") (pintype "passive"))
      (node (ref "R88") (pin "S") (pinfunction "S_S") (pintype "passive"))
    )
    (net (code "180") (name "Net-(Q17-E)") (class "Default")
      (node (ref "Q17") (pin "1") (pinfunction "E_1") (pintype "passive"))
      (node (ref "R90") (pin "2") (pinfunction "2_2") (pintype "passive"))
    )
    (net (code "181") (name "Net-(Q18-C)") (class "Default")
      (node (ref "D28") (pin "A") (pinfunction "A_A") (pintype "passive"))
      (node (ref "Q18") (pin "3") (pinfunction "C_3") (pintype "passive"))
      (node (ref "R86") (pin "E") (pinfunction "E_E") (pintype "passive"))
      (node (ref "R86") (pin "S") (pinfunction "S_S") (pintype "passive"))
    )
    (net (code "182") (name "Net-(Q18-E)") (class "Default")
      (node (ref "Q18") (pin "1") (pinfunction "E_1") (pintype "passive"))
      (node (ref "R91") (pin "2") (pinfunction "2_2") (pintype "passive"))
    )
    (net (code "183") (name "Net-(Q19-B)") (class "Default")
      (node (ref "Q19") (pin "2") (pinfunction "B_2") (pintype "passive"))
      (node (ref "R95") (pin "2") (pinfunction "2_2") (pintype "passive"))
    )
    (net (code "184") (name "Net-(Q19-C)") (class "Default")
      (node (ref "D30") (pin "C") (pinfunction "C_C") (pintype "passive"))
      (node (ref "Q19") (pin "3") (pinfunction "C_3") (pintype "passive"))
      (node (ref "R96") (pin "1") (pinfunction "1_1") (pintype "passive"))
      (node (ref "R97") (pin "2") (pinfunction "2_2") (pintype "passive"))
    )
    (net (code "185") (name "Net-(Q20-B)") (class "Default")
      (node (ref "Q20") (pin "2") (pinfunction "B_2") (pintype "passive"))
      (node (ref "R100") (pin "2") (pinfunction "2_2") (pintype "passive"))
    )
    (net (code "186") (name "Net-(Q20-C)") (class "Default")
      (node (ref "D33") (pin "C") (pinfunction "C_C") (pintype "passive"))
      (node (ref "Q20") (pin "3") (pinfunction "C_3") (pintype "passive"))
      (node (ref "R101") (pin "1") (pinfunction "1_1") (pintype "passive"))
      (node (ref "R102") (pin "2") (pinfunction "2_2") (pintype "passive"))
    )
    (net (code "187") (name "Net-(Q21-B)") (class "Default")
      (node (ref "Q21") (pin "2") (pinfunction "B_2") (pintype "passive"))
      (node (ref "R105") (pin "2") (pinfunction "2_2") (pintype "passive"))
    )
    (net (code "188") (name "Net-(Q21-C)") (class "Default")
      (node (ref "D37") (pin "A") (pinfunction "A_A") (pintype "passive"))
      (node (ref "Q21") (pin "3") (pinfunction "C_3") (pintype "passive"))
      (node (ref "R107") (pin "1") (pinfunction "1_1") (pintype "passive"))
    )
    (net (code "189") (name "Net-(Q22-B)") (class "Default")
      (node (ref "Q22") (pin "2") (pinfunction "B_2") (pintype "passive"))
      (node (ref "R108") (pin "2") (pinfunction "2_2") (pintype "passive"))
    )
    (net (code "190") (name "Net-(Q22-C)") (class "Default")
      (node (ref "D39") (pin "A") (pinfunction "A_A") (pintype "passive"))
      (node (ref "Q22") (pin "3") (pinfunction "C_3") (pintype "passive"))
      (node (ref "R110") (pin "1") (pinfunction "1_1") (pintype "passive"))
    )
    (net (code "191") (name "Net-(Q23-B)") (class "Default")
      (node (ref "Q23") (pin "2") (pinfunction "B_2") (pintype "passive"))
      (node (ref "R111") (pin "2") (pinfunction "2_2") (pintype "passive"))
    )
    (net (code "192") (name "Net-(Q23-C)") (class "Default")
      (node (ref "D41") (pin "A") (pinfunction "A_A") (pintype "passive"))
      (node (ref "Q23") (pin "3") (pinfunction "C_3") (pintype "passive"))
      (node (ref "R113") (pin "1") (pinfunction "1_1") (pintype "passive"))
    )
    (net (code "193") (name "Net-(Q24-B)") (class "Default")
      (node (ref "Q24") (pin "2") (pinfunction "B_2") (pintype "passive"))
      (node (ref "R114") (pin "2") (pinfunction "2_2") (pintype "passive"))
    )
    (net (code "194") (name "Net-(Q24-C)") (class "Default")
      (node (ref "D43") (pin "A") (pinfunction "A_A") (pintype "passive"))
      (node (ref "Q24") (pin "3") (pinfunction "C_3") (pintype "passive"))
      (node (ref "R118") (pin "1") (pinfunction "1_1") (pintype "passive"))
    )
    (net (code "195") (name "Net-(Q25-B)") (class "Default")
      (node (ref "Q25") (pin "2") (pinfunction "B_2") (pintype "passive"))
      (node (ref "R119") (pin "2") (pinfunction "2_2") (pintype "passive"))
    )
    (net (code "196") (name "Net-(Q25-C)") (class "Default")
      (node (ref "D45") (pin "A") (pinfunction "A_A") (pintype "passive"))
      (node (ref "Q25") (pin "3") (pinfunction "C_3") (pintype "passive"))
      (node (ref "R122") (pin "1") (pinfunction "1_1") (pintype "passive"))
    )
    (net (code "197") (name "Net-(Q26-B)") (class "Default")
      (node (ref "Q26") (pin "2") (pinfunction "B_2") (pintype "passive"))
      (node (ref "R123") (pin "2") (pinfunction "2_2") (pintype "passive"))
    )
    (net (code "198") (name "Net-(Q26-C)") (class "Default")
      (node (ref "D47") (pin "A") (pinfunction "A_A") (pintype "passive"))
      (node (ref "Q26") (pin "3") (pinfunction "C_3") (pintype "passive"))
      (node (ref "R126") (pin "1") (pinfunction "1_1") (pintype "passive"))
    )
    (net (code "199") (name "Net-(Q27-B)") (class "Default")
      (node (ref "Q27") (pin "2") (pinfunction "B_2") (pintype "passive"))
      (node (ref "R127") (pin "2") (pinfunction "2_2") (pintype "passive"))
    )
    (net (code "200") (name "Net-(Q27-C)") (class "Default")
      (node (ref "D49") (pin "A") (pinfunction "A_A") (pintype "passive"))
      (node (ref "Q27") (pin "3") (pinfunction "C_3") (pintype "passive"))
      (node (ref "R130") (pin "1") (pinfunction "1_1") (pintype "passive"))
    )
    (net (code "201") (name "Net-(Q28-B)") (class "Default")
      (node (ref "Q28") (pin "2") (pinfunction "B_2") (pintype "passive"))
      (node (ref "R131") (pin "2") (pinfunction "2_2") (pintype "passive"))
    )
    (net (code "202") (name "Net-(Q28-C)") (class "Default")
      (node (ref "D51") (pin "A") (pinfunction "A_A") (pintype "passive"))
      (node (ref "Q28") (pin "3") (pinfunction "C_3") (pintype "passive"))
      (node (ref "R134") (pin "1") (pinfunction "1_1") (pintype "passive"))
      (node (ref "R135") (pin "1") (pinfunction "1_1") (pintype "passive"))
    )
    (net (code "203") (name "Net-(Q29-B)") (class "Default")
      (node (ref "D52") (pin "A") (pinfunction "A_A") (pintype "passive"))
      (node (ref "Q29") (pin "2") (pinfunction "B_2") (pintype "passive"))
      (node (ref "R136") (pin "1") (pinfunction "1_1") (pintype "passive"))
    )
    (net (code "204") (name "Net-(Q29-C)") (class "Default")
      (node (ref "C37") (pin "1") (pinfunction "1_1") (pintype "passive"))
      (node (ref "Q29") (pin "3") (pinfunction "C_3") (pintype "passive"))
      (node (ref "R137") (pin "1") (pinfunction "1_1") (pintype "passive"))
    )
    (net (code "205") (name "Net-(Q29-E)") (class "Default")
      (node (ref "Q29") (pin "1") (pinfunction "E_1") (pintype "passive"))
      (node (ref "R140") (pin "1") (pinfunction "1_1") (pintype "passive"))
    )
    (net (code "206") (name "Net-(Q30-B)") (class "Default")
      (node (ref "D53") (pin "A") (pinfunction "A_A") (pintype "passive"))
      (node (ref "Q30") (pin "2") (pinfunction "B_2") (pintype "passive"))
      (node (ref "R145") (pin "2") (pinfunction "2_2") (pintype "passive"))
    )
    (net (code "207") (name "Net-(Q30-C)") (class "Default")
      (node (ref "C39") (pin "2") (pinfunction "2_2") (pintype "passive"))
      (node (ref "Q30") (pin "3") (pinfunction "C_3") (pintype "passive"))
      (node (ref "R146") (pin "2") (pinfunction "2_2") (pintype "passive"))
    )
    (net (code "208") (name "Net-(Q30-E)") (class "Default")
      (node (ref "Q30") (pin "1") (pinfunction "E_1") (pintype "passive"))
      (node (ref "R144") (pin "1") (pinfunction "1_1") (pintype "passive"))
    )
    (net (code "209") (name "Net-(R29-PadA)") (class "Default")
      (node (ref "R29") (pin "A") (pinfunction "A_A") (pintype "passive"))
      (node (ref "R29") (pin "S") (pinfunction "S_S") (pintype "passive"))
      (node (ref "R30") (pin "2") (pinfunction "2_2") (pintype "passive"))
      (node (ref "W3") (pin "2") (pinfunction "2_2") (pintype "passive"))
    )
    (net (code "210") (name "Net-(R30-Pad1)") (class "Default")
      (node (ref "R30") (pin "1") (pinfunction "1_1") (pintype "passive"))
      (node (ref "R31") (pin "2") (pinfunction "2_2") (pintype "passive"))
    )
    (net (code "211") (name "Net-(R34-PadA)") (class "Default")
      (node (ref "R34") (pin "A") (pinfunction "A_A") (pintype "passive"))
      (node (ref "R34") (pin "S") (pinfunction "S_S") (pintype "passive"))
      (node (ref "R35") (pin "2") (pinfunction "2_2") (pintype "passive"))
    )
    (net (code "212") (name "Net-(R38-PadA)") (class "Default")
      (node (ref "R38") (pin "A") (pinfunction "A_A") (pintype "passive"))
      (node (ref "R38") (pin "S") (pinfunction "S_S") (pintype "passive"))
      (node (ref "R39") (pin "2") (pinfunction "2_2") (pintype "passive"))
    )
    (net (code "213") (name "Net-(R42-PadA)") (class "Default")
      (node (ref "R42") (pin "A") (pinfunction "A_A") (pintype "passive"))
      (node (ref "R42") (pin "S") (pinfunction "S_S") (pintype "passive"))
      (node (ref "R43") (pin "2") (pinfunction "2_2") (pintype "passive"))
    )
    (net (code "214") (name "Net-(R46-PadA)") (class "Default")
      (node (ref "R46") (pin "A") (pinfunction "A_A") (pintype "passive"))
      (node (ref "R46") (pin "S") (pinfunction "S_S") (pintype "passive"))
      (node (ref "R47") (pin "2") (pinfunction "2_2") (pintype "passive"))
      (node (ref "R48") (pin "2") (pinfunction "2_2") (pintype "passive"))
    )
    (net (code "215") (name "Net-(R58-Pad2)") (class "Default")
      (node (ref "R58") (pin "2") (pinfunction "2_2") (pintype "passive"))
      (node (ref "W1") (pin "1") (pinfunction "1_1") (pintype "passive"))
    )
    (net (code "216") (name "Net-(R59-Pad2)") (class "Default")
      (node (ref "R59") (pin "2") (pinfunction "2_2") (pintype "passive"))
      (node (ref "W4") (pin "1") (pinfunction "1_1") (pintype "passive"))
    )
    (net (code "217") (name "Net-(R61-Pad1)") (class "Default")
      (node (ref "R61") (pin "1") (pinfunction "1_1") (pintype "passive"))
      (node (ref "W1") (pin "2") (pinfunction "2_2") (pintype "passive"))
      (node (ref "W4") (pin "2") (pinfunction "2_2") (pintype "passive"))
    )
    (net (code "218") (name "Net-(R83-Pad2)") (class "Default")
      (node (ref "R83") (pin "2") (pinfunction "2_2") (pintype "passive"))
      (node (ref "R84") (pin "1") (pinfunction "1_1") (pintype "passive"))
      (node (ref "W5") (pin "1") (pinfunction "1_1") (pintype "passive"))
    )
    (net (code "219") (name "Net-(R85-Pad1)") (class "Default")
      (node (ref "R85") (pin "1") (pinfunction "1_1") (pintype "passive"))
      (node (ref "R86") (pin "A") (pinfunction "A_A") (pintype "passive"))
    )
    (net (code "220") (name "Net-(R88-PadE)") (class "Default")
      (node (ref "R88") (pin "E") (pinfunction "E_E") (pintype "passive"))
      (node (ref "R92") (pin "1") (pinfunction "1_1") (pintype "passive"))
    )
    (net (code "221") (name "Net-(R116-PadA)") (class "Default")
      (node (ref "R116") (pin "A") (pinfunction "A_A") (pintype "passive"))
      (node (ref "R116") (pin "S") (pinfunction "S_S") (pintype "passive"))
      (node (ref "R117") (pin "2") (pinfunction "2_2") (pintype "passive"))
      (node (ref "W2") (pin "2") (pinfunction "2_2") (pintype "passive"))
    )
    (net (code "222") (name "Net-(R117-Pad1)") (class "Default")
      (node (ref "R117") (pin "1") (pinfunction "1_1") (pintype "passive"))
      (node (ref "R118") (pin "2") (pinfunction "2_2") (pintype "passive"))
    )
    (net (code "223") (name "Net-(R121-PadA)") (class "Default")
      (node (ref "R121") (pin "A") (pinfunction "A_A") (pintype "passive"))
      (node (ref "R121") (pin "S") (pinfunction "S_S") (pintype "passive"))
      (node (ref "R122") (pin "2") (pinfunction "2_2") (pintype "passive"))
    )
    (net (code "224") (name "Net-(R125-PadA)") (class "Default")
      (node (ref "R125") (pin "A") (pinfunction "A_A") (pintype "passive"))
      (node (ref "R125") (pin "S") (pinfunction "S_S") (pintype "passive"))
      (node (ref "R126") (pin "2") (pinfunction "2_2") (pintype "passive"))
    )
    (net (code "225") (name "Net-(R129-PadA)") (class "Default")
      (node (ref "R129") (pin "A") (pinfunction "A_A") (pintype "passive"))
      (node (ref "R129") (pin "S") (pinfunction "S_S") (pintype "passive"))
      (node (ref "R130") (pin "2") (pinfunction "2_2") (pintype "passive"))
    )
    (net (code "226") (name "Net-(R133-PadA)") (class "Default")
      (node (ref "R133") (pin "A") (pinfunction "A_A") (pintype "passive"))
      (node (ref "R133") (pin "S") (pinfunction "S_S") (pintype "passive"))
      (node (ref "R134") (pin "2") (pinfunction "2_2") (pintype "passive"))
      (node (ref "R135") (pin "2") (pinfunction "2_2") (pintype "passive"))
    )
    (net (code "227") (name "Net-(R148-Pad2)") (class "Default")
      (node (ref "R148") (pin "2") (pinfunction "2_2") (pintype "passive"))
      (node (ref "R149") (pin "1") (pinfunction "1_1") (pintype "passive"))
      (node (ref "W6") (pin "1") (pinfunction "1_1") (pintype "passive"))
    )
    (net (code "228") (name "VCC") (class "Default")
      (node (ref "C1") (pin "1") (pinfunction "1_1") (pintype "passive"))
      (node (ref "C10") (pin "1") (pinfunction "1_1") (pintype "passive"))
      (node (ref "C11") (pin "1") (pinfunction "1_1") (pintype "passive"))
      (node (ref "C12") (pin "1") (pinfunction "1_1") (pintype "passive"))
      (node (ref "C13") (pin "1") (pinfunction "1_1") (pintype "passive"))
      (node (ref "C14") (pin "+") (pinfunction "+_+") (pintype "passive"))
      (node (ref "C16") (pin "+") (pinfunction "+_+") (pintype "passive"))
      (node (ref "C18") (pin "+") (pinfunction "+_+") (pintype "passive"))
      (node (ref "C2") (pin "1") (pinfunction "1_1") (pintype "passive"))
      (node (ref "C3") (pin "1") (pinfunction "1_1") (pintype "passive"))
      (node (ref "C4") (pin "1") (pinfunction "1_1") (pintype "passive"))
      (node (ref "C5") (pin "1") (pinfunction "1_1") (pintype "passive"))
      (node (ref "C6") (pin "1") (pinfunction "1_1") (pintype "passive"))
      (node (ref "C7") (pin "1") (pinfunction "1_1") (pintype "passive"))
      (node (ref "C8") (pin "1") (pinfunction "1_1") (pintype "passive"))
      (node (ref "C9") (pin "1") (pinfunction "1_1") (pintype "passive"))
      (node (ref "OMNIBUS") (pin "AA2") (pinfunction "1_AA2") (pintype "bidirectional"))
      (node (ref "OMNIBUS") (pin "BA2") (pinfunction "1_BA2") (pintype "bidirectional"))
      (node (ref "OMNIBUS") (pin "CA2") (pinfunction "1_CA2") (pintype "bidirectional"))
      (node (ref "Q12") (pin "1") (pinfunction "E_1") (pintype "passive"))
      (node (ref "R1") (pin "2") (pinfunction "2_2") (pintype "passive"))
      (node (ref "R101") (pin "2") (pinfunction "2_2") (pintype "passive"))
      (node (ref "R14") (pin "2") (pinfunction "2_2") (pintype "passive"))
      (node (ref "R2") (pin "2") (pinfunction "2_2") (pintype "passive"))
      (node (ref "R3") (pin "2") (pinfunction "2_2") (pintype "passive"))
      (node (ref "R4") (pin "2") (pinfunction "2_2") (pintype "passive"))
      (node (ref "R5") (pin "2") (pinfunction "2_2") (pintype "passive"))
      (node (ref "R56") (pin "2") (pinfunction "2_2") (pintype "passive"))
      (node (ref "R58") (pin "1") (pinfunction "1_1") (pintype "passive"))
      (node (ref "R59") (pin "1") (pinfunction "1_1") (pintype "passive"))
      (node (ref "R6") (pin "2") (pinfunction "2_2") (pintype "passive"))
      (node (ref "R60") (pin "2") (pinfunction "2_2") (pintype "passive"))
      (node (ref "R7") (pin "2") (pinfunction "2_2") (pintype "passive"))
      (node (ref "R9") (pin "2") (pinfunction "2_2") (pintype "passive"))
      (node (ref "R96") (pin "2") (pinfunction "2_2") (pintype "passive"))
    )
    (net (code "229") (name "unconnected-(E1A-BO-Pad13)") (class "Default")
      (node (ref "E1") (pin "13") (pinfunction "BO_13") (pintype "output"))
    )
    (net (code "230") (name "unconnected-(E1A-CO-Pad12)") (class "Default")
      (node (ref "E1") (pin "12") (pinfunction "CO_12") (pintype "output"))
    )
    (net (code "231") (name "unconnected-(E1A-QC-Pad6)") (class "Default")
      (node (ref "E1") (pin "6") (pinfunction "QC_6") (pintype "output"))
    )
    (net (code "232") (name "unconnected-(E1A-QD-Pad7)") (class "Default")
      (node (ref "E1") (pin "7") (pinfunction "QD_7") (pintype "output"))
    )
    (net (code "233") (name "unconnected-(E2A-BO-Pad13)") (class "Default")
      (node (ref "E2") (pin "13") (pinfunction "BO_13") (pintype "output"))
    )
    (net (code "234") (name "unconnected-(E2A-CO-Pad12)") (class "Default")
      (node (ref "E2") (pin "12") (pinfunction "CO_12") (pintype "output"))
    )
    (net (code "235") (name "unconnected-(E2A-QC-Pad6)") (class "Default")
      (node (ref "E2") (pin "6") (pinfunction "QC_6") (pintype "output"))
    )
    (net (code "236") (name "unconnected-(E2A-QD-Pad7)") (class "Default")
      (node (ref "E2") (pin "7") (pinfunction "QD_7") (pintype "output"))
    )
    (net (code "237") (name "unconnected-(E13A-A2-Pad10)") (class "Default")
      (node (ref "E13") (pin "10") (pinfunction "A2_10") (pintype "input"))
    )
    (net (code "238") (name "unconnected-(E13A-A3-Pad15)") (class "Default")
      (node (ref "E13") (pin "15") (pinfunction "A3_15") (pintype "input"))
    )
    (net (code "239") (name "unconnected-(E13A-B2-Pad11)") (class "Default")
      (node (ref "E13") (pin "11") (pinfunction "B2_11") (pintype "input"))
    )
    (net (code "240") (name "unconnected-(E13A-B3-Pad14)") (class "Default")
      (node (ref "E13") (pin "14") (pinfunction "B3_14") (pintype "input"))
    )
    (net (code "241") (name "unconnected-(E13A-F2-Pad12)") (class "Default")
      (node (ref "E13") (pin "12") (pinfunction "F2_12") (pintype "open_collector"))
    )
    (net (code "242") (name "unconnected-(E13A-F3-Pad13)") (class "Default")
      (node (ref "E13") (pin "13") (pinfunction "F3_13") (pintype "open_collector"))
    )
    (net (code "243") (name "unconnected-(E14--IN-Pad2)") (class "Default")
      (node (ref "E14") (pin "2") (pinfunction "-IN_2") (pintype "input"))
    )
    (net (code "244") (name "unconnected-(E14-ON1-Pad1)") (class "Default")
      (node (ref "E14") (pin "1") (pinfunction "ON1_1") (pintype "passive"))
    )
    (net (code "245") (name "unconnected-(E14-ON2-Pad8)") (class "Default")
      (node (ref "E14") (pin "8") (pinfunction "ON2_8") (pintype "passive"))
    )
    (net (code "246") (name "unconnected-(E14-OPT-Pad5)") (class "Default")
      (node (ref "E14") (pin "5") (pinfunction "OPT_5") (pintype "passive"))
    )
    (net (code "247") (name "unconnected-(E15--IN-Pad2)") (class "Default")
      (node (ref "E15") (pin "2") (pinfunction "-IN_2") (pintype "input"))
    )
    (net (code "248") (name "unconnected-(E15-ON1-Pad1)") (class "Default")
      (node (ref "E15") (pin "1") (pinfunction "ON1_1") (pintype "passive"))
    )
    (net (code "249") (name "unconnected-(E15-ON2-Pad8)") (class "Default")
      (node (ref "E15") (pin "8") (pinfunction "ON2_8") (pintype "passive"))
    )
    (net (code "250") (name "unconnected-(E15-OPT-Pad5)") (class "Default")
      (node (ref "E15") (pin "5") (pinfunction "OPT_5") (pintype "passive"))
    )
    (net (code "251") (name "unconnected-(J1-2-PadB)") (class "Default")
      (node (ref "J1") (pin "B") (pinfunction "2_B") (pintype "bidirectional"))
    )
    (net (code "252") (name "unconnected-(J1-14-PadR)") (class "Default")
      (node (ref "J1") (pin "R") (pinfunction "14_R") (pintype "bidirectional"))
    )
    (net (code "253") (name "unconnected-(J1-16-PadT)") (class "Default")
      (node (ref "J1") (pin "T") (pinfunction "16_T") (pintype "bidirectional"))
    )
    (net (code "254") (name "unconnected-(J1-36-PadRR)") (class "Default")
      (node (ref "J1") (pin "RR") (pinfunction "36_RR") (pintype "bidirectional"))
    )
    (net (code "255") (name "unconnected-(J1-38-PadTT)") (class "Default")
      (node (ref "J1") (pin "TT") (pinfunction "38_TT") (pintype "bidirectional"))
    )
    (net (code "256") (name "unconnected-(J1-40-PadVV)") (class "Default")
      (node (ref "J1") (pin "VV") (pinfunction "40_VV") (pintype "bidirectional"))
    )
    (net (code "257") (name "unconnected-(TP1-PadTP)") (class "Default")
      (node (ref "TP1") (pin "TP") (pinfunction "TP_TP") (pintype "input"))
    )
    (net (code "258") (name "unconnected-(TP2-PadTP)") (class "Default")
      (node (ref "TP2") (pin "TP") (pinfunction "TP_TP") (pintype "input"))
    )
  )
)
